# mem.net
KiCad netlist of a schematic drawn in EAGLE
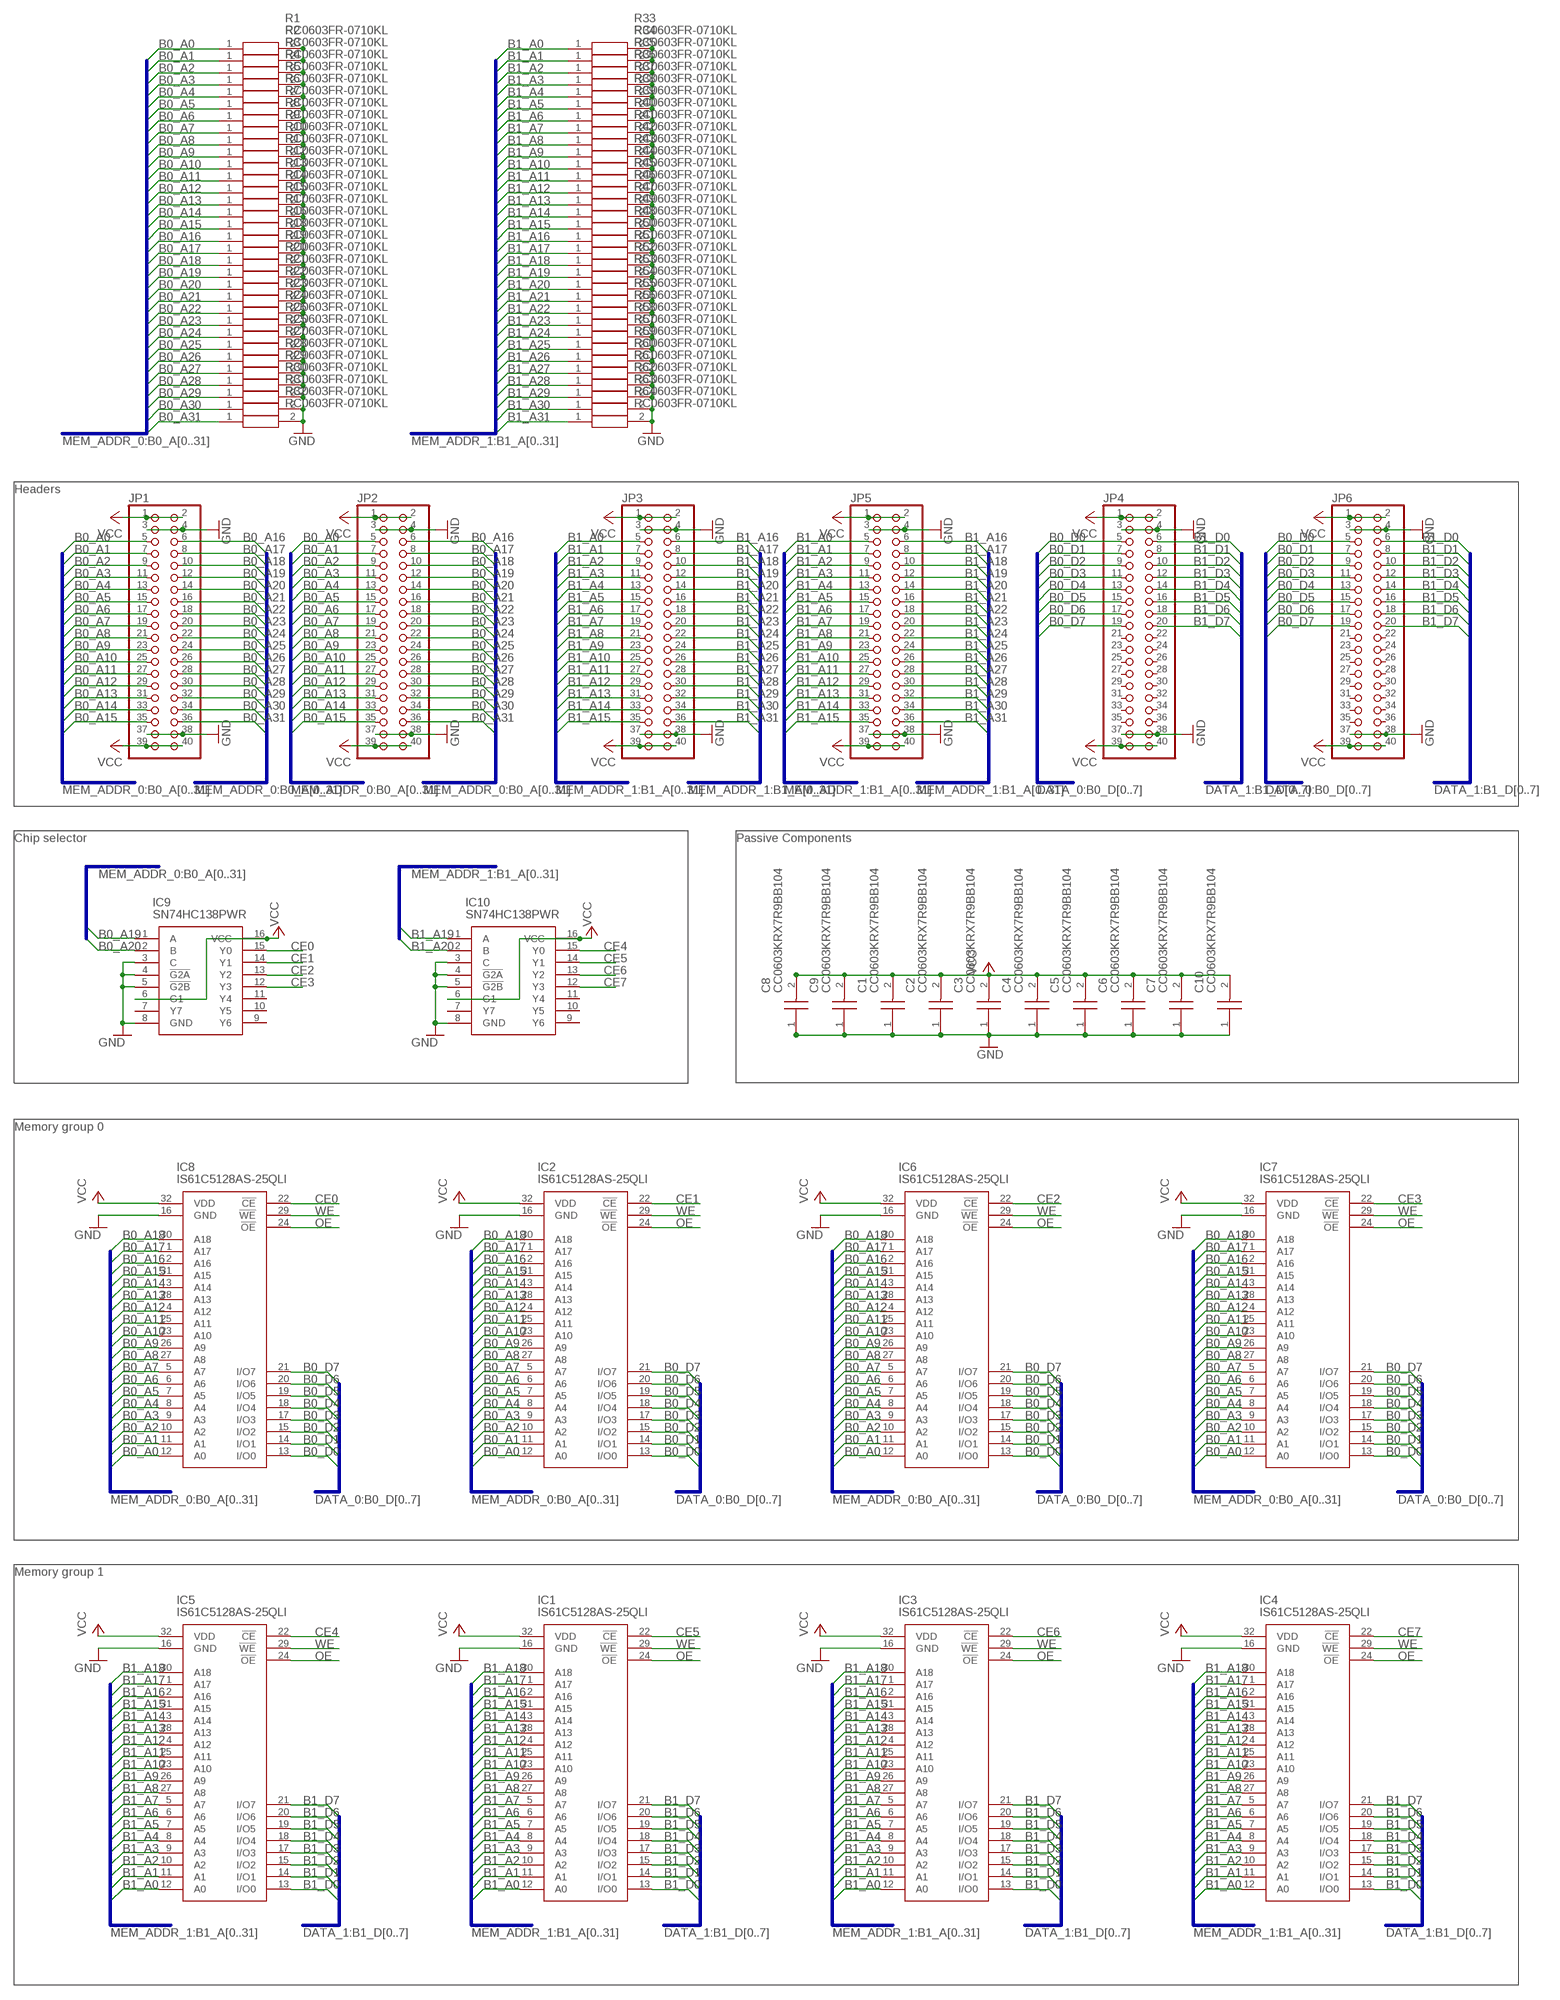
[diagram p0: schematic, sheet 1]

(export (version "E")
  (design (tool "Eeschema 10.0.6"))
  (components
    (comp (ref "C1")
      (value "CC0603KRX7R9BB104")
      (footprint "eagle-import:CAPC1608X90N")
      (fields (field (name "MOUSER_PART_NUMBER") "603-CC603KRX7R9BB104"))
      (libsource (lib "eagle-import") (part "CC0603KRX7R9BB104"))
    )
    (comp (ref "C2")
      (value "CC0603KRX7R9BB104")
      (footprint "eagle-import:CAPC1608X90N")
      (fields (field (name "MOUSER_PART_NUMBER") "603-CC603KRX7R9BB104"))
      (libsource (lib "eagle-import") (part "CC0603KRX7R9BB104"))
    )
    (comp (ref "C3")
      (value "CC0603KRX7R9BB104")
      (footprint "eagle-import:CAPC1608X90N")
      (fields (field (name "MOUSER_PART_NUMBER") "603-CC603KRX7R9BB104"))
      (libsource (lib "eagle-import") (part "CC0603KRX7R9BB104"))
    )
    (comp (ref "C4")
      (value "CC0603KRX7R9BB104")
      (footprint "eagle-import:CAPC1608X90N")
      (fields (field (name "MOUSER_PART_NUMBER") "603-CC603KRX7R9BB104"))
      (libsource (lib "eagle-import") (part "CC0603KRX7R9BB104"))
    )
    (comp (ref "C5")
      (value "CC0603KRX7R9BB104")
      (footprint "eagle-import:CAPC1608X90N")
      (fields (field (name "MOUSER_PART_NUMBER") "603-CC603KRX7R9BB104"))
      (libsource (lib "eagle-import") (part "CC0603KRX7R9BB104"))
    )
    (comp (ref "C6")
      (value "CC0603KRX7R9BB104")
      (footprint "eagle-import:CAPC1608X90N")
      (fields (field (name "MOUSER_PART_NUMBER") "603-CC603KRX7R9BB104"))
      (libsource (lib "eagle-import") (part "CC0603KRX7R9BB104"))
    )
    (comp (ref "C7")
      (value "CC0603KRX7R9BB104")
      (footprint "eagle-import:CAPC1608X90N")
      (fields (field (name "MOUSER_PART_NUMBER") "603-CC603KRX7R9BB104"))
      (libsource (lib "eagle-import") (part "CC0603KRX7R9BB104"))
    )
    (comp (ref "C8")
      (value "CC0603KRX7R9BB104")
      (footprint "eagle-import:CAPC1608X90N")
      (fields (field (name "MOUSER_PART_NUMBER") "603-CC603KRX7R9BB104"))
      (libsource (lib "eagle-import") (part "CC0603KRX7R9BB104"))
    )
    (comp (ref "C9")
      (value "CC0603KRX7R9BB104")
      (footprint "eagle-import:CAPC1608X90N")
      (fields (field (name "MOUSER_PART_NUMBER") "603-CC603KRX7R9BB104"))
      (libsource (lib "eagle-import") (part "CC0603KRX7R9BB104"))
    )
    (comp (ref "C10")
      (value "CC0603KRX7R9BB104")
      (footprint "eagle-import:CAPC1608X90N")
      (fields (field (name "MOUSER_PART_NUMBER") "603-CC603KRX7R9BB104"))
      (libsource (lib "eagle-import") (part "CC0603KRX7R9BB104"))
    )
    (comp (ref "IC1")
      (value "IS61C5128AS-25QLI")
      (footprint "eagle-import:SOIC127P1412X305-32N")
      (fields (field (name "MOUSER_PART_NUMBER") "870-61C5128AS-25QLI"))
      (libsource (lib "eagle-import") (part "IS61C5128AS-25QLI"))
    )
    (comp (ref "IC2")
      (value "IS61C5128AS-25QLI")
      (footprint "eagle-import:SOIC127P1412X305-32N")
      (fields (field (name "MOUSER_PART_NUMBER") "870-61C5128AS-25QLI"))
      (libsource (lib "eagle-import") (part "IS61C5128AS-25QLI"))
    )
    (comp (ref "IC3")
      (value "IS61C5128AS-25QLI")
      (footprint "eagle-import:SOIC127P1412X305-32N")
      (fields (field (name "MOUSER_PART_NUMBER") "870-61C5128AS-25QLI"))
      (libsource (lib "eagle-import") (part "IS61C5128AS-25QLI"))
    )
    (comp (ref "IC4")
      (value "IS61C5128AS-25QLI")
      (footprint "eagle-import:SOIC127P1412X305-32N")
      (fields (field (name "MOUSER_PART_NUMBER") "870-61C5128AS-25QLI"))
      (libsource (lib "eagle-import") (part "IS61C5128AS-25QLI"))
    )
    (comp (ref "IC5")
      (value "IS61C5128AS-25QLI")
      (footprint "eagle-import:SOIC127P1412X305-32N")
      (fields (field (name "MOUSER_PART_NUMBER") "870-61C5128AS-25QLI"))
      (libsource (lib "eagle-import") (part "IS61C5128AS-25QLI"))
    )
    (comp (ref "IC6")
      (value "IS61C5128AS-25QLI")
      (footprint "eagle-import:SOIC127P1412X305-32N")
      (fields (field (name "MOUSER_PART_NUMBER") "870-61C5128AS-25QLI"))
      (libsource (lib "eagle-import") (part "IS61C5128AS-25QLI"))
    )
    (comp (ref "IC7")
      (value "IS61C5128AS-25QLI")
      (footprint "eagle-import:SOIC127P1412X305-32N")
      (fields (field (name "MOUSER_PART_NUMBER") "870-61C5128AS-25QLI"))
      (libsource (lib "eagle-import") (part "IS61C5128AS-25QLI"))
    )
    (comp (ref "IC8")
      (value "IS61C5128AS-25QLI")
      (footprint "eagle-import:SOIC127P1412X305-32N")
      (fields (field (name "MOUSER_PART_NUMBER") "870-61C5128AS-25QLI"))
      (libsource (lib "eagle-import") (part "IS61C5128AS-25QLI"))
    )
    (comp (ref "IC9")
      (value "SN74HC138PWR")
      (footprint "eagle-import:SOP65P640X120-16N")
      (fields (field (name "MOUSER_PART_NUMBER") "595-SN74HC138PWR"))
      (libsource (lib "eagle-import") (part "SN74HC138PWR"))
    )
    (comp (ref "IC10")
      (value "SN74HC138PWR")
      (footprint "eagle-import:SOP65P640X120-16N")
      (fields (field (name "MOUSER_PART_NUMBER") "595-SN74HC138PWR"))
      (libsource (lib "eagle-import") (part "SN74HC138PWR"))
    )
    (comp (ref "JP1")
      (value "PINHD-2X20")
      (footprint "eagle-import:2X20")
      (libsource (lib "eagle-import") (part "PINHD-2X20"))
    )
    (comp (ref "JP2")
      (value "PINHD-2X20")
      (footprint "eagle-import:2X20")
      (libsource (lib "eagle-import") (part "PINHD-2X20"))
    )
    (comp (ref "JP3")
      (value "PINHD-2X20")
      (footprint "eagle-import:2X20")
      (libsource (lib "eagle-import") (part "PINHD-2X20"))
    )
    (comp (ref "JP4")
      (value "PINHD-2X20")
      (footprint "eagle-import:2X20")
      (libsource (lib "eagle-import") (part "PINHD-2X20"))
    )
    (comp (ref "JP5")
      (value "PINHD-2X20")
      (footprint "eagle-import:2X20")
      (libsource (lib "eagle-import") (part "PINHD-2X20"))
    )
    (comp (ref "JP6")
      (value "PINHD-2X20")
      (footprint "eagle-import:2X20")
      (libsource (lib "eagle-import") (part "PINHD-2X20"))
    )
    (comp (ref "R1")
      (value "RC0603FR-0710KL")
      (footprint "eagle-import:RESC1608X55N")
      (fields (field (name "MOUSER_PART_NUMBER") "603-RC0603FR-0710KL"))
      (libsource (lib "eagle-import") (part "RC0603FR-0710KL"))
    )
    (comp (ref "R2")
      (value "RC0603FR-0710KL")
      (footprint "eagle-import:RESC1608X55N")
      (fields (field (name "MOUSER_PART_NUMBER") "603-RC0603FR-0710KL"))
      (libsource (lib "eagle-import") (part "RC0603FR-0710KL"))
    )
    (comp (ref "R3")
      (value "RC0603FR-0710KL")
      (footprint "eagle-import:RESC1608X55N")
      (fields (field (name "MOUSER_PART_NUMBER") "603-RC0603FR-0710KL"))
      (libsource (lib "eagle-import") (part "RC0603FR-0710KL"))
    )
    (comp (ref "R4")
      (value "RC0603FR-0710KL")
      (footprint "eagle-import:RESC1608X55N")
      (fields (field (name "MOUSER_PART_NUMBER") "603-RC0603FR-0710KL"))
      (libsource (lib "eagle-import") (part "RC0603FR-0710KL"))
    )
    (comp (ref "R5")
      (value "RC0603FR-0710KL")
      (footprint "eagle-import:RESC1608X55N")
      (fields (field (name "MOUSER_PART_NUMBER") "603-RC0603FR-0710KL"))
      (libsource (lib "eagle-import") (part "RC0603FR-0710KL"))
    )
    (comp (ref "R6")
      (value "RC0603FR-0710KL")
      (footprint "eagle-import:RESC1608X55N")
      (fields (field (name "MOUSER_PART_NUMBER") "603-RC0603FR-0710KL"))
      (libsource (lib "eagle-import") (part "RC0603FR-0710KL"))
    )
    (comp (ref "R7")
      (value "RC0603FR-0710KL")
      (footprint "eagle-import:RESC1608X55N")
      (fields (field (name "MOUSER_PART_NUMBER") "603-RC0603FR-0710KL"))
      (libsource (lib "eagle-import") (part "RC0603FR-0710KL"))
    )
    (comp (ref "R8")
      (value "RC0603FR-0710KL")
      (footprint "eagle-import:RESC1608X55N")
      (fields (field (name "MOUSER_PART_NUMBER") "603-RC0603FR-0710KL"))
      (libsource (lib "eagle-import") (part "RC0603FR-0710KL"))
    )
    (comp (ref "R9")
      (value "RC0603FR-0710KL")
      (footprint "eagle-import:RESC1608X55N")
      (fields (field (name "MOUSER_PART_NUMBER") "603-RC0603FR-0710KL"))
      (libsource (lib "eagle-import") (part "RC0603FR-0710KL"))
    )
    (comp (ref "R10")
      (value "RC0603FR-0710KL")
      (footprint "eagle-import:RESC1608X55N")
      (fields (field (name "MOUSER_PART_NUMBER") "603-RC0603FR-0710KL"))
      (libsource (lib "eagle-import") (part "RC0603FR-0710KL"))
    )
    (comp (ref "R11")
      (value "RC0603FR-0710KL")
      (footprint "eagle-import:RESC1608X55N")
      (fields (field (name "MOUSER_PART_NUMBER") "603-RC0603FR-0710KL"))
      (libsource (lib "eagle-import") (part "RC0603FR-0710KL"))
    )
    (comp (ref "R12")
      (value "RC0603FR-0710KL")
      (footprint "eagle-import:RESC1608X55N")
      (fields (field (name "MOUSER_PART_NUMBER") "603-RC0603FR-0710KL"))
      (libsource (lib "eagle-import") (part "RC0603FR-0710KL"))
    )
    (comp (ref "R13")
      (value "RC0603FR-0710KL")
      (footprint "eagle-import:RESC1608X55N")
      (fields (field (name "MOUSER_PART_NUMBER") "603-RC0603FR-0710KL"))
      (libsource (lib "eagle-import") (part "RC0603FR-0710KL"))
    )
    (comp (ref "R14")
      (value "RC0603FR-0710KL")
      (footprint "eagle-import:RESC1608X55N")
      (fields (field (name "MOUSER_PART_NUMBER") "603-RC0603FR-0710KL"))
      (libsource (lib "eagle-import") (part "RC0603FR-0710KL"))
    )
    (comp (ref "R15")
      (value "RC0603FR-0710KL")
      (footprint "eagle-import:RESC1608X55N")
      (fields (field (name "MOUSER_PART_NUMBER") "603-RC0603FR-0710KL"))
      (libsource (lib "eagle-import") (part "RC0603FR-0710KL"))
    )
    (comp (ref "R16")
      (value "RC0603FR-0710KL")
      (footprint "eagle-import:RESC1608X55N")
      (fields (field (name "MOUSER_PART_NUMBER") "603-RC0603FR-0710KL"))
      (libsource (lib "eagle-import") (part "RC0603FR-0710KL"))
    )
    (comp (ref "R17")
      (value "RC0603FR-0710KL")
      (footprint "eagle-import:RESC1608X55N")
      (fields (field (name "MOUSER_PART_NUMBER") "603-RC0603FR-0710KL"))
      (libsource (lib "eagle-import") (part "RC0603FR-0710KL"))
    )
    (comp (ref "R18")
      (value "RC0603FR-0710KL")
      (footprint "eagle-import:RESC1608X55N")
      (fields (field (name "MOUSER_PART_NUMBER") "603-RC0603FR-0710KL"))
      (libsource (lib "eagle-import") (part "RC0603FR-0710KL"))
    )
    (comp (ref "R19")
      (value "RC0603FR-0710KL")
      (footprint "eagle-import:RESC1608X55N")
      (fields (field (name "MOUSER_PART_NUMBER") "603-RC0603FR-0710KL"))
      (libsource (lib "eagle-import") (part "RC0603FR-0710KL"))
    )
    (comp (ref "R20")
      (value "RC0603FR-0710KL")
      (footprint "eagle-import:RESC1608X55N")
      (fields (field (name "MOUSER_PART_NUMBER") "603-RC0603FR-0710KL"))
      (libsource (lib "eagle-import") (part "RC0603FR-0710KL"))
    )
    (comp (ref "R21")
      (value "RC0603FR-0710KL")
      (footprint "eagle-import:RESC1608X55N")
      (fields (field (name "MOUSER_PART_NUMBER") "603-RC0603FR-0710KL"))
      (libsource (lib "eagle-import") (part "RC0603FR-0710KL"))
    )
    (comp (ref "R22")
      (value "RC0603FR-0710KL")
      (footprint "eagle-import:RESC1608X55N")
      (fields (field (name "MOUSER_PART_NUMBER") "603-RC0603FR-0710KL"))
      (libsource (lib "eagle-import") (part "RC0603FR-0710KL"))
    )
    (comp (ref "R23")
      (value "RC0603FR-0710KL")
      (footprint "eagle-import:RESC1608X55N")
      (fields (field (name "MOUSER_PART_NUMBER") "603-RC0603FR-0710KL"))
      (libsource (lib "eagle-import") (part "RC0603FR-0710KL"))
    )
    (comp (ref "R24")
      (value "RC0603FR-0710KL")
      (footprint "eagle-import:RESC1608X55N")
      (fields (field (name "MOUSER_PART_NUMBER") "603-RC0603FR-0710KL"))
      (libsource (lib "eagle-import") (part "RC0603FR-0710KL"))
    )
    (comp (ref "R25")
      (value "RC0603FR-0710KL")
      (footprint "eagle-import:RESC1608X55N")
      (fields (field (name "MOUSER_PART_NUMBER") "603-RC0603FR-0710KL"))
      (libsource (lib "eagle-import") (part "RC0603FR-0710KL"))
    )
    (comp (ref "R26")
      (value "RC0603FR-0710KL")
      (footprint "eagle-import:RESC1608X55N")
      (fields (field (name "MOUSER_PART_NUMBER") "603-RC0603FR-0710KL"))
      (libsource (lib "eagle-import") (part "RC0603FR-0710KL"))
    )
    (comp (ref "R27")
      (value "RC0603FR-0710KL")
      (footprint "eagle-import:RESC1608X55N")
      (fields (field (name "MOUSER_PART_NUMBER") "603-RC0603FR-0710KL"))
      (libsource (lib "eagle-import") (part "RC0603FR-0710KL"))
    )
    (comp (ref "R28")
      (value "RC0603FR-0710KL")
      (footprint "eagle-import:RESC1608X55N")
      (fields (field (name "MOUSER_PART_NUMBER") "603-RC0603FR-0710KL"))
      (libsource (lib "eagle-import") (part "RC0603FR-0710KL"))
    )
    (comp (ref "R29")
      (value "RC0603FR-0710KL")
      (footprint "eagle-import:RESC1608X55N")
      (fields (field (name "MOUSER_PART_NUMBER") "603-RC0603FR-0710KL"))
      (libsource (lib "eagle-import") (part "RC0603FR-0710KL"))
    )
    (comp (ref "R30")
      (value "RC0603FR-0710KL")
      (footprint "eagle-import:RESC1608X55N")
      (fields (field (name "MOUSER_PART_NUMBER") "603-RC0603FR-0710KL"))
      (libsource (lib "eagle-import") (part "RC0603FR-0710KL"))
    )
    (comp (ref "R31")
      (value "RC0603FR-0710KL")
      (footprint "eagle-import:RESC1608X55N")
      (fields (field (name "MOUSER_PART_NUMBER") "603-RC0603FR-0710KL"))
      (libsource (lib "eagle-import") (part "RC0603FR-0710KL"))
    )
    (comp (ref "R32")
      (value "RC0603FR-0710KL")
      (footprint "eagle-import:RESC1608X55N")
      (fields (field (name "MOUSER_PART_NUMBER") "603-RC0603FR-0710KL"))
      (libsource (lib "eagle-import") (part "RC0603FR-0710KL"))
    )
    (comp (ref "R33")
      (value "RC0603FR-0710KL")
      (footprint "eagle-import:RESC1608X55N")
      (fields (field (name "MOUSER_PART_NUMBER") "603-RC0603FR-0710KL"))
      (libsource (lib "eagle-import") (part "RC0603FR-0710KL"))
    )
    (comp (ref "R34")
      (value "RC0603FR-0710KL")
      (footprint "eagle-import:RESC1608X55N")
      (fields (field (name "MOUSER_PART_NUMBER") "603-RC0603FR-0710KL"))
      (libsource (lib "eagle-import") (part "RC0603FR-0710KL"))
    )
    (comp (ref "R35")
      (value "RC0603FR-0710KL")
      (footprint "eagle-import:RESC1608X55N")
      (fields (field (name "MOUSER_PART_NUMBER") "603-RC0603FR-0710KL"))
      (libsource (lib "eagle-import") (part "RC0603FR-0710KL"))
    )
    (comp (ref "R36")
      (value "RC0603FR-0710KL")
      (footprint "eagle-import:RESC1608X55N")
      (fields (field (name "MOUSER_PART_NUMBER") "603-RC0603FR-0710KL"))
      (libsource (lib "eagle-import") (part "RC0603FR-0710KL"))
    )
    (comp (ref "R37")
      (value "RC0603FR-0710KL")
      (footprint "eagle-import:RESC1608X55N")
      (fields (field (name "MOUSER_PART_NUMBER") "603-RC0603FR-0710KL"))
      (libsource (lib "eagle-import") (part "RC0603FR-0710KL"))
    )
    (comp (ref "R38")
      (value "RC0603FR-0710KL")
      (footprint "eagle-import:RESC1608X55N")
      (fields (field (name "MOUSER_PART_NUMBER") "603-RC0603FR-0710KL"))
      (libsource (lib "eagle-import") (part "RC0603FR-0710KL"))
    )
    (comp (ref "R39")
      (value "RC0603FR-0710KL")
      (footprint "eagle-import:RESC1608X55N")
      (fields (field (name "MOUSER_PART_NUMBER") "603-RC0603FR-0710KL"))
      (libsource (lib "eagle-import") (part "RC0603FR-0710KL"))
    )
    (comp (ref "R40")
      (value "RC0603FR-0710KL")
      (footprint "eagle-import:RESC1608X55N")
      (fields (field (name "MOUSER_PART_NUMBER") "603-RC0603FR-0710KL"))
      (libsource (lib "eagle-import") (part "RC0603FR-0710KL"))
    )
    (comp (ref "R41")
      (value "RC0603FR-0710KL")
      (footprint "eagle-import:RESC1608X55N")
      (fields (field (name "MOUSER_PART_NUMBER") "603-RC0603FR-0710KL"))
      (libsource (lib "eagle-import") (part "RC0603FR-0710KL"))
    )
    (comp (ref "R42")
      (value "RC0603FR-0710KL")
      (footprint "eagle-import:RESC1608X55N")
      (fields (field (name "MOUSER_PART_NUMBER") "603-RC0603FR-0710KL"))
      (libsource (lib "eagle-import") (part "RC0603FR-0710KL"))
    )
    (comp (ref "R43")
      (value "RC0603FR-0710KL")
      (footprint "eagle-import:RESC1608X55N")
      (fields (field (name "MOUSER_PART_NUMBER") "603-RC0603FR-0710KL"))
      (libsource (lib "eagle-import") (part "RC0603FR-0710KL"))
    )
    (comp (ref "R44")
      (value "RC0603FR-0710KL")
      (footprint "eagle-import:RESC1608X55N")
      (fields (field (name "MOUSER_PART_NUMBER") "603-RC0603FR-0710KL"))
      (libsource (lib "eagle-import") (part "RC0603FR-0710KL"))
    )
    (comp (ref "R45")
      (value "RC0603FR-0710KL")
      (footprint "eagle-import:RESC1608X55N")
      (fields (field (name "MOUSER_PART_NUMBER") "603-RC0603FR-0710KL"))
      (libsource (lib "eagle-import") (part "RC0603FR-0710KL"))
    )
    (comp (ref "R46")
      (value "RC0603FR-0710KL")
      (footprint "eagle-import:RESC1608X55N")
      (fields (field (name "MOUSER_PART_NUMBER") "603-RC0603FR-0710KL"))
      (libsource (lib "eagle-import") (part "RC0603FR-0710KL"))
    )
    (comp (ref "R47")
      (value "RC0603FR-0710KL")
      (footprint "eagle-import:RESC1608X55N")
      (fields (field (name "MOUSER_PART_NUMBER") "603-RC0603FR-0710KL"))
      (libsource (lib "eagle-import") (part "RC0603FR-0710KL"))
    )
    (comp (ref "R48")
      (value "RC0603FR-0710KL")
      (footprint "eagle-import:RESC1608X55N")
      (fields (field (name "MOUSER_PART_NUMBER") "603-RC0603FR-0710KL"))
      (libsource (lib "eagle-import") (part "RC0603FR-0710KL"))
    )
    (comp (ref "R49")
      (value "RC0603FR-0710KL")
      (footprint "eagle-import:RESC1608X55N")
      (fields (field (name "MOUSER_PART_NUMBER") "603-RC0603FR-0710KL"))
      (libsource (lib "eagle-import") (part "RC0603FR-0710KL"))
    )
    (comp (ref "R50")
      (value "RC0603FR-0710KL")
      (footprint "eagle-import:RESC1608X55N")
      (fields (field (name "MOUSER_PART_NUMBER") "603-RC0603FR-0710KL"))
      (libsource (lib "eagle-import") (part "RC0603FR-0710KL"))
    )
    (comp (ref "R51")
      (value "RC0603FR-0710KL")
      (footprint "eagle-import:RESC1608X55N")
      (fields (field (name "MOUSER_PART_NUMBER") "603-RC0603FR-0710KL"))
      (libsource (lib "eagle-import") (part "RC0603FR-0710KL"))
    )
    (comp (ref "R52")
      (value "RC0603FR-0710KL")
      (footprint "eagle-import:RESC1608X55N")
      (fields (field (name "MOUSER_PART_NUMBER") "603-RC0603FR-0710KL"))
      (libsource (lib "eagle-import") (part "RC0603FR-0710KL"))
    )
    (comp (ref "R53")
      (value "RC0603FR-0710KL")
      (footprint "eagle-import:RESC1608X55N")
      (fields (field (name "MOUSER_PART_NUMBER") "603-RC0603FR-0710KL"))
      (libsource (lib "eagle-import") (part "RC0603FR-0710KL"))
    )
    (comp (ref "R54")
      (value "RC0603FR-0710KL")
      (footprint "eagle-import:RESC1608X55N")
      (fields (field (name "MOUSER_PART_NUMBER") "603-RC0603FR-0710KL"))
      (libsource (lib "eagle-import") (part "RC0603FR-0710KL"))
    )
    (comp (ref "R55")
      (value "RC0603FR-0710KL")
      (footprint "eagle-import:RESC1608X55N")
      (fields (field (name "MOUSER_PART_NUMBER") "603-RC0603FR-0710KL"))
      (libsource (lib "eagle-import") (part "RC0603FR-0710KL"))
    )
    (comp (ref "R56")
      (value "RC0603FR-0710KL")
      (footprint "eagle-import:RESC1608X55N")
      (fields (field (name "MOUSER_PART_NUMBER") "603-RC0603FR-0710KL"))
      (libsource (lib "eagle-import") (part "RC0603FR-0710KL"))
    )
    (comp (ref "R57")
      (value "RC0603FR-0710KL")
      (footprint "eagle-import:RESC1608X55N")
      (fields (field (name "MOUSER_PART_NUMBER") "603-RC0603FR-0710KL"))
      (libsource (lib "eagle-import") (part "RC0603FR-0710KL"))
    )
    (comp (ref "R58")
      (value "RC0603FR-0710KL")
      (footprint "eagle-import:RESC1608X55N")
      (fields (field (name "MOUSER_PART_NUMBER") "603-RC0603FR-0710KL"))
      (libsource (lib "eagle-import") (part "RC0603FR-0710KL"))
    )
    (comp (ref "R59")
      (value "RC0603FR-0710KL")
      (footprint "eagle-import:RESC1608X55N")
      (fields (field (name "MOUSER_PART_NUMBER") "603-RC0603FR-0710KL"))
      (libsource (lib "eagle-import") (part "RC0603FR-0710KL"))
    )
    (comp (ref "R60")
      (value "RC0603FR-0710KL")
      (footprint "eagle-import:RESC1608X55N")
      (fields (field (name "MOUSER_PART_NUMBER") "603-RC0603FR-0710KL"))
      (libsource (lib "eagle-import") (part "RC0603FR-0710KL"))
    )
    (comp (ref "R61")
      (value "RC0603FR-0710KL")
      (footprint "eagle-import:RESC1608X55N")
      (fields (field (name "MOUSER_PART_NUMBER") "603-RC0603FR-0710KL"))
      (libsource (lib "eagle-import") (part "RC0603FR-0710KL"))
    )
    (comp (ref "R62")
      (value "RC0603FR-0710KL")
      (footprint "eagle-import:RESC1608X55N")
      (fields (field (name "MOUSER_PART_NUMBER") "603-RC0603FR-0710KL"))
      (libsource (lib "eagle-import") (part "RC0603FR-0710KL"))
    )
    (comp (ref "R63")
      (value "RC0603FR-0710KL")
      (footprint "eagle-import:RESC1608X55N")
      (fields (field (name "MOUSER_PART_NUMBER") "603-RC0603FR-0710KL"))
      (libsource (lib "eagle-import") (part "RC0603FR-0710KL"))
    )
    (comp (ref "R64")
      (value "RC0603FR-0710KL")
      (footprint "eagle-import:RESC1608X55N")
      (fields (field (name "MOUSER_PART_NUMBER") "603-RC0603FR-0710KL"))
      (libsource (lib "eagle-import") (part "RC0603FR-0710KL"))
    )
  )
  (nets
    (net (code "81") (name "/B0_A0") (class "Default")
      (node (ref "IC2") (pin "12") (pinfunction "A0_12") (pintype "bidirectional"))
      (node (ref "IC6") (pin "12") (pinfunction "A0_12") (pintype "bidirectional"))
      (node (ref "IC7") (pin "12") (pinfunction "A0_12") (pintype "bidirectional"))
      (node (ref "IC8") (pin "12") (pinfunction "A0_12") (pintype "bidirectional"))
      (node (ref "JP1") (pin "5") (pinfunction "5_5") (pintype "passive"))
      (node (ref "JP2") (pin "5") (pinfunction "5_5") (pintype "passive"))
      (node (ref "R1") (pin "1") (pinfunction "1_1") (pintype "bidirectional"))
    )
    (net (code "82") (name "/B0_A1") (class "Default")
      (node (ref "IC2") (pin "11") (pinfunction "A1_11") (pintype "bidirectional"))
      (node (ref "IC6") (pin "11") (pinfunction "A1_11") (pintype "bidirectional"))
      (node (ref "IC7") (pin "11") (pinfunction "A1_11") (pintype "bidirectional"))
      (node (ref "IC8") (pin "11") (pinfunction "A1_11") (pintype "bidirectional"))
      (node (ref "JP1") (pin "7") (pinfunction "7_7") (pintype "passive"))
      (node (ref "JP2") (pin "7") (pinfunction "7_7") (pintype "passive"))
      (node (ref "R2") (pin "1") (pinfunction "1_1") (pintype "bidirectional"))
    )
    (net (code "83") (name "/B0_A2") (class "Default")
      (node (ref "IC2") (pin "10") (pinfunction "A2_10") (pintype "bidirectional"))
      (node (ref "IC6") (pin "10") (pinfunction "A2_10") (pintype "bidirectional"))
      (node (ref "IC7") (pin "10") (pinfunction "A2_10") (pintype "bidirectional"))
      (node (ref "IC8") (pin "10") (pinfunction "A2_10") (pintype "bidirectional"))
      (node (ref "JP1") (pin "9") (pinfunction "9_9") (pintype "passive"))
      (node (ref "JP2") (pin "9") (pinfunction "9_9") (pintype "passive"))
      (node (ref "R3") (pin "1") (pinfunction "1_1") (pintype "bidirectional"))
    )
    (net (code "84") (name "/B0_A3") (class "Default")
      (node (ref "IC2") (pin "9") (pinfunction "A3_9") (pintype "bidirectional"))
      (node (ref "IC6") (pin "9") (pinfunction "A3_9") (pintype "bidirectional"))
      (node (ref "IC7") (pin "9") (pinfunction "A3_9") (pintype "bidirectional"))
      (node (ref "IC8") (pin "9") (pinfunction "A3_9") (pintype "bidirectional"))
      (node (ref "JP1") (pin "11") (pinfunction "11_11") (pintype "passive"))
      (node (ref "JP2") (pin "11") (pinfunction "11_11") (pintype "passive"))
      (node (ref "R4") (pin "1") (pinfunction "1_1") (pintype "bidirectional"))
    )
    (net (code "85") (name "/B0_A4") (class "Default")
      (node (ref "IC2") (pin "8") (pinfunction "A4_8") (pintype "bidirectional"))
      (node (ref "IC6") (pin "8") (pinfunction "A4_8") (pintype "bidirectional"))
      (node (ref "IC7") (pin "8") (pinfunction "A4_8") (pintype "bidirectional"))
      (node (ref "IC8") (pin "8") (pinfunction "A4_8") (pintype "bidirectional"))
      (node (ref "JP1") (pin "13") (pinfunction "13_13") (pintype "passive"))
      (node (ref "JP2") (pin "13") (pinfunction "13_13") (pintype "passive"))
      (node (ref "R5") (pin "1") (pinfunction "1_1") (pintype "bidirectional"))
    )
    (net (code "86") (name "/B0_A5") (class "Default")
      (node (ref "IC2") (pin "7") (pinfunction "A5_7") (pintype "bidirectional"))
      (node (ref "IC6") (pin "7") (pinfunction "A5_7") (pintype "bidirectional"))
      (node (ref "IC7") (pin "7") (pinfunction "A5_7") (pintype "bidirectional"))
      (node (ref "IC8") (pin "7") (pinfunction "A5_7") (pintype "bidirectional"))
      (node (ref "JP1") (pin "15") (pinfunction "15_15") (pintype "passive"))
      (node (ref "JP2") (pin "15") (pinfunction "15_15") (pintype "passive"))
      (node (ref "R6") (pin "1") (pinfunction "1_1") (pintype "bidirectional"))
    )
    (net (code "87") (name "/B0_A6") (class "Default")
      (node (ref "IC2") (pin "6") (pinfunction "A6_6") (pintype "bidirectional"))
      (node (ref "IC6") (pin "6") (pinfunction "A6_6") (pintype "bidirectional"))
      (node (ref "IC7") (pin "6") (pinfunction "A6_6") (pintype "bidirectional"))
      (node (ref "IC8") (pin "6") (pinfunction "A6_6") (pintype "bidirectional"))
      (node (ref "JP1") (pin "17") (pinfunction "17_17") (pintype "passive"))
      (node (ref "JP2") (pin "17") (pinfunction "17_17") (pintype "passive"))
      (node (ref "R7") (pin "1") (pinfunction "1_1") (pintype "bidirectional"))
    )
    (net (code "88") (name "/B0_A7") (class "Default")
      (node (ref "IC2") (pin "5") (pinfunction "A7_5") (pintype "bidirectional"))
      (node (ref "IC6") (pin "5") (pinfunction "A7_5") (pintype "bidirectional"))
      (node (ref "IC7") (pin "5") (pinfunction "A7_5") (pintype "bidirectional"))
      (node (ref "IC8") (pin "5") (pinfunction "A7_5") (pintype "bidirectional"))
      (node (ref "JP1") (pin "19") (pinfunction "19_19") (pintype "passive"))
      (node (ref "JP2") (pin "19") (pinfunction "19_19") (pintype "passive"))
      (node (ref "R8") (pin "1") (pinfunction "1_1") (pintype "bidirectional"))
    )
    (net (code "89") (name "/B0_A8") (class "Default")
      (node (ref "IC2") (pin "27") (pinfunction "A8_27") (pintype "bidirectional"))
      (node (ref "IC6") (pin "27") (pinfunction "A8_27") (pintype "bidirectional"))
      (node (ref "IC7") (pin "27") (pinfunction "A8_27") (pintype "bidirectional"))
      (node (ref "IC8") (pin "27") (pinfunction "A8_27") (pintype "bidirectional"))
      (node (ref "JP1") (pin "21") (pinfunction "21_21") (pintype "passive"))
      (node (ref "JP2") (pin "21") (pinfunction "21_21") (pintype "passive"))
      (node (ref "R9") (pin "1") (pinfunction "1_1") (pintype "bidirectional"))
    )
    (net (code "90") (name "/B0_A9") (class "Default")
      (node (ref "IC2") (pin "26") (pinfunction "A9_26") (pintype "bidirectional"))
      (node (ref "IC6") (pin "26") (pinfunction "A9_26") (pintype "bidirectional"))
      (node (ref "IC7") (pin "26") (pinfunction "A9_26") (pintype "bidirectional"))
      (node (ref "IC8") (pin "26") (pinfunction "A9_26") (pintype "bidirectional"))
      (node (ref "JP1") (pin "23") (pinfunction "23_23") (pintype "passive"))
      (node (ref "JP2") (pin "23") (pinfunction "23_23") (pintype "passive"))
      (node (ref "R10") (pin "1") (pinfunction "1_1") (pintype "bidirectional"))
    )
    (net (code "91") (name "/B0_A10") (class "Default")
      (node (ref "IC2") (pin "23") (pinfunction "A10_23") (pintype "bidirectional"))
      (node (ref "IC6") (pin "23") (pinfunction "A10_23") (pintype "bidirectional"))
      (node (ref "IC7") (pin "23") (pinfunction "A10_23") (pintype "bidirectional"))
      (node (ref "IC8") (pin "23") (pinfunction "A10_23") (pintype "bidirectional"))
      (node (ref "JP1") (pin "25") (pinfunction "25_25") (pintype "passive"))
      (node (ref "JP2") (pin "25") (pinfunction "25_25") (pintype "passive"))
      (node (ref "R11") (pin "1") (pinfunction "1_1") (pintype "bidirectional"))
    )
    (net (code "92") (name "/B0_A11") (class "Default")
      (node (ref "IC2") (pin "25") (pinfunction "A11_25") (pintype "bidirectional"))
      (node (ref "IC6") (pin "25") (pinfunction "A11_25") (pintype "bidirectional"))
      (node (ref "IC7") (pin "25") (pinfunction "A11_25") (pintype "bidirectional"))
      (node (ref "IC8") (pin "25") (pinfunction "A11_25") (pintype "bidirectional"))
      (node (ref "JP1") (pin "27") (pinfunction "27_27") (pintype "passive"))
      (node (ref "JP2") (pin "27") (pinfunction "27_27") (pintype "passive"))
      (node (ref "R12") (pin "1") (pinfunction "1_1") (pintype "bidirectional"))
    )
    (net (code "93") (name "/B0_A12") (class "Default")
      (node (ref "IC2") (pin "4") (pinfunction "A12_4") (pintype "bidirectional"))
      (node (ref "IC6") (pin "4") (pinfunction "A12_4") (pintype "bidirectional"))
      (node (ref "IC7") (pin "4") (pinfunction "A12_4") (pintype "bidirectional"))
      (node (ref "IC8") (pin "4") (pinfunction "A12_4") (pintype "bidirectional"))
      (node (ref "JP1") (pin "29") (pinfunction "29_29") (pintype "passive"))
      (node (ref "JP2") (pin "29") (pinfunction "29_29") (pintype "passive"))
      (node (ref "R13") (pin "1") (pinfunction "1_1") (pintype "bidirectional"))
    )
    (net (code "94") (name "/B0_A13") (class "Default")
      (node (ref "IC2") (pin "28") (pinfunction "A13_28") (pintype "bidirectional"))
      (node (ref "IC6") (pin "28") (pinfunction "A13_28") (pintype "bidirectional"))
      (node (ref "IC7") (pin "28") (pinfunction "A13_28") (pintype "bidirectional"))
      (node (ref "IC8") (pin "28") (pinfunction "A13_28") (pintype "bidirectional"))
      (node (ref "JP1") (pin "31") (pinfunction "31_31") (pintype "passive"))
      (node (ref "JP2") (pin "31") (pinfunction "31_31") (pintype "passive"))
      (node (ref "R14") (pin "1") (pinfunction "1_1") (pintype "bidirectional"))
    )
    (net (code "95") (name "/B0_A14") (class "Default")
      (node (ref "IC2") (pin "3") (pinfunction "A14_3") (pintype "bidirectional"))
      (node (ref "IC6") (pin "3") (pinfunction "A14_3") (pintype "bidirectional"))
      (node (ref "IC7") (pin "3") (pinfunction "A14_3") (pintype "bidirectional"))
      (node (ref "IC8") (pin "3") (pinfunction "A14_3") (pintype "bidirectional"))
      (node (ref "JP1") (pin "33") (pinfunction "33_33") (pintype "passive"))
      (node (ref "JP2") (pin "33") (pinfunction "33_33") (pintype "passive"))
      (node (ref "R15") (pin "1") (pinfunction "1_1") (pintype "bidirectional"))
    )
    (net (code "96") (name "/B0_A15") (class "Default")
      (node (ref "IC2") (pin "31") (pinfunction "A15_31") (pintype "bidirectional"))
      (node (ref "IC6") (pin "31") (pinfunction "A15_31") (pintype "bidirectional"))
      (node (ref "IC7") (pin "31") (pinfunction "A15_31") (pintype "bidirectional"))
      (node (ref "IC8") (pin "31") (pinfunction "A15_31") (pintype "bidirectional"))
      (node (ref "JP1") (pin "35") (pinfunction "35_35") (pintype "passive"))
      (node (ref "JP2") (pin "35") (pinfunction "35_35") (pintype "passive"))
      (node (ref "R17") (pin "1") (pinfunction "1_1") (pintype "bidirectional"))
    )
    (net (code "97") (name "/B0_A16") (class "Default")
      (node (ref "IC2") (pin "2") (pinfunction "A16_2") (pintype "bidirectional"))
      (node (ref "IC6") (pin "2") (pinfunction "A16_2") (pintype "bidirectional"))
      (node (ref "IC7") (pin "2") (pinfunction "A16_2") (pintype "bidirectional"))
      (node (ref "IC8") (pin "2") (pinfunction "A16_2") (pintype "bidirectional"))
      (node (ref "JP1") (pin "6") (pinfunction "6_6") (pintype "passive"))
      (node (ref "JP2") (pin "6") (pinfunction "6_6") (pintype "passive"))
      (node (ref "R16") (pin "1") (pinfunction "1_1") (pintype "bidirectional"))
    )
    (net (code "98") (name "/B0_A17") (class "Default")
      (node (ref "IC2") (pin "1") (pinfunction "A17_1") (pintype "bidirectional"))
      (node (ref "IC6") (pin "1") (pinfunction "A17_1") (pintype "bidirectional"))
      (node (ref "IC7") (pin "1") (pinfunction "A17_1") (pintype "bidirectional"))
      (node (ref "IC8") (pin "1") (pinfunction "A17_1") (pintype "bidirectional"))
      (node (ref "JP1") (pin "8") (pinfunction "8_8") (pintype "passive"))
      (node (ref "JP2") (pin "8") (pinfunction "8_8") (pintype "passive"))
      (node (ref "R18") (pin "1") (pinfunction "1_1") (pintype "bidirectional"))
    )
    (net (code "99") (name "/B0_A18") (class "Default")
      (node (ref "IC2") (pin "30") (pinfunction "A18_30") (pintype "bidirectional"))
      (node (ref "IC6") (pin "30") (pinfunction "A18_30") (pintype "bidirectional"))
      (node (ref "IC7") (pin "30") (pinfunction "A18_30") (pintype "bidirectional"))
      (node (ref "IC8") (pin "30") (pinfunction "A18_30") (pintype "bidirectional"))
      (node (ref "JP1") (pin "10") (pinfunction "10_10") (pintype "passive"))
      (node (ref "JP2") (pin "10") (pinfunction "10_10") (pintype "passive"))
      (node (ref "R19") (pin "1") (pinfunction "1_1") (pintype "bidirectional"))
    )
    (net (code "100") (name "/B0_A19") (class "Default")
      (node (ref "IC9") (pin "1") (pinfunction "A_1") (pintype "bidirectional"))
      (node (ref "JP1") (pin "12") (pinfunction "12_12") (pintype "passive"))
      (node (ref "JP2") (pin "12") (pinfunction "12_12") (pintype "passive"))
      (node (ref "R20") (pin "1") (pinfunction "1_1") (pintype "bidirectional"))
    )
    (net (code "101") (name "/B0_A20") (class "Default")
      (node (ref "IC9") (pin "2") (pinfunction "B_2") (pintype "bidirectional"))
      (node (ref "JP1") (pin "14") (pinfunction "14_14") (pintype "passive"))
      (node (ref "JP2") (pin "14") (pinfunction "14_14") (pintype "passive"))
      (node (ref "R21") (pin "1") (pinfunction "1_1") (pintype "bidirectional"))
    )
    (net (code "102") (name "/B0_A21") (class "Default")
      (node (ref "JP1") (pin "16") (pinfunction "16_16") (pintype "passive"))
      (node (ref "JP2") (pin "16") (pinfunction "16_16") (pintype "passive"))
      (node (ref "R22") (pin "1") (pinfunction "1_1") (pintype "bidirectional"))
    )
    (net (code "103") (name "/B0_A22") (class "Default")
      (node (ref "JP1") (pin "18") (pinfunction "18_18") (pintype "passive"))
      (node (ref "JP2") (pin "18") (pinfunction "18_18") (pintype "passive"))
      (node (ref "R23") (pin "1") (pinfunction "1_1") (pintype "bidirectional"))
    )
    (net (code "104") (name "/B0_A23") (class "Default")
      (node (ref "JP1") (pin "20") (pinfunction "20_20") (pintype "passive"))
      (node (ref "JP2") (pin "20") (pinfunction "20_20") (pintype "passive"))
      (node (ref "R24") (pin "1") (pinfunction "1_1") (pintype "bidirectional"))
    )
    (net (code "105") (name "/B0_A24") (class "Default")
      (node (ref "JP1") (pin "22") (pinfunction "22_22") (pintype "passive"))
      (node (ref "JP2") (pin "22") (pinfunction "22_22") (pintype "passive"))
      (node (ref "R26") (pin "1") (pinfunction "1_1") (pintype "bidirectional"))
    )
    (net (code "106") (name "/B0_A25") (class "Default")
      (node (ref "JP1") (pin "24") (pinfunction "24_24") (pintype "passive"))
      (node (ref "JP2") (pin "24") (pinfunction "24_24") (pintype "passive"))
      (node (ref "R25") (pin "1") (pinfunction "1_1") (pintype "bidirectional"))
    )
    (net (code "107") (name "/B0_A26") (class "Default")
      (node (ref "JP1") (pin "26") (pinfunction "26_26") (pintype "passive"))
      (node (ref "JP2") (pin "26") (pinfunction "26_26") (pintype "passive"))
      (node (ref "R27") (pin "1") (pinfunction "1_1") (pintype "bidirectional"))
    )
    (net (code "108") (name "/B0_A27") (class "Default")
      (node (ref "JP1") (pin "28") (pinfunction "28_28") (pintype "passive"))
      (node (ref "JP2") (pin "28") (pinfunction "28_28") (pintype "passive"))
      (node (ref "R28") (pin "1") (pinfunction "1_1") (pintype "bidirectional"))
    )
    (net (code "109") (name "/B0_A28") (class "Default")
      (node (ref "JP1") (pin "30") (pinfunction "30_30") (pintype "passive"))
      (node (ref "JP2") (pin "30") (pinfunction "30_30") (pintype "passive"))
      (node (ref "R29") (pin "1") (pinfunction "1_1") (pintype "bidirectional"))
    )
    (net (code "110") (name "/B0_A29") (class "Default")
      (node (ref "JP1") (pin "32") (pinfunction "32_32") (pintype "passive"))
      (node (ref "JP2") (pin "32") (pinfunction "32_32") (pintype "passive"))
      (node (ref "R30") (pin "1") (pinfunction "1_1") (pintype "bidirectional"))
    )
    (net (code "111") (name "/B0_A30") (class "Default")
      (node (ref "JP1") (pin "34") (pinfunction "34_34") (pintype "passive"))
      (node (ref "JP2") (pin "34") (pinfunction "34_34") (pintype "passive"))
      (node (ref "R31") (pin "1") (pinfunction "1_1") (pintype "bidirectional"))
    )
    (net (code "112") (name "/B0_A31") (class "Default")
      (node (ref "JP1") (pin "36") (pinfunction "36_36") (pintype "passive"))
      (node (ref "JP2") (pin "36") (pinfunction "36_36") (pintype "passive"))
      (node (ref "R32") (pin "1") (pinfunction "1_1") (pintype "bidirectional"))
    )
    (net (code "113") (name "/B0_D0") (class "Default")
      (node (ref "IC2") (pin "13") (pinfunction "I/O0_13") (pintype "bidirectional"))
      (node (ref "IC6") (pin "13") (pinfunction "I/O0_13") (pintype "bidirectional"))
      (node (ref "IC7") (pin "13") (pinfunction "I/O0_13") (pintype "bidirectional"))
      (node (ref "IC8") (pin "13") (pinfunction "I/O0_13") (pintype "bidirectional"))
      (node (ref "JP4") (pin "5") (pinfunction "5_5") (pintype "passive"))
      (node (ref "JP6") (pin "5") (pinfunction "5_5") (pintype "passive"))
    )
    (net (code "114") (name "/B0_D1") (class "Default")
      (node (ref "IC2") (pin "14") (pinfunction "I/O1_14") (pintype "bidirectional"))
      (node (ref "IC6") (pin "14") (pinfunction "I/O1_14") (pintype "bidirectional"))
      (node (ref "IC7") (pin "14") (pinfunction "I/O1_14") (pintype "bidirectional"))
      (node (ref "IC8") (pin "14") (pinfunction "I/O1_14") (pintype "bidirectional"))
      (node (ref "JP4") (pin "7") (pinfunction "7_7") (pintype "passive"))
      (node (ref "JP6") (pin "7") (pinfunction "7_7") (pintype "passive"))
    )
    (net (code "115") (name "/B0_D2") (class "Default")
      (node (ref "IC2") (pin "15") (pinfunction "I/O2_15") (pintype "bidirectional"))
      (node (ref "IC6") (pin "15") (pinfunction "I/O2_15") (pintype "bidirectional"))
      (node (ref "IC7") (pin "15") (pinfunction "I/O2_15") (pintype "bidirectional"))
      (node (ref "IC8") (pin "15") (pinfunction "I/O2_15") (pintype "bidirectional"))
      (node (ref "JP4") (pin "9") (pinfunction "9_9") (pintype "passive"))
      (node (ref "JP6") (pin "9") (pinfunction "9_9") (pintype "passive"))
    )
    (net (code "116") (name "/B0_D3") (class "Default")
      (node (ref "IC2") (pin "17") (pinfunction "I/O3_17") (pintype "bidirectional"))
      (node (ref "IC6") (pin "17") (pinfunction "I/O3_17") (pintype "bidirectional"))
      (node (ref "IC7") (pin "17") (pinfunction "I/O3_17") (pintype "bidirectional"))
      (node (ref "IC8") (pin "17") (pinfunction "I/O3_17") (pintype "bidirectional"))
      (node (ref "JP4") (pin "11") (pinfunction "11_11") (pintype "passive"))
      (node (ref "JP6") (pin "11") (pinfunction "11_11") (pintype "passive"))
    )
    (net (code "117") (name "/B0_D4") (class "Default")
      (node (ref "IC2") (pin "18") (pinfunction "I/O4_18") (pintype "bidirectional"))
      (node (ref "IC6") (pin "18") (pinfunction "I/O4_18") (pintype "bidirectional"))
      (node (ref "IC7") (pin "18") (pinfunction "I/O4_18") (pintype "bidirectional"))
      (node (ref "IC8") (pin "18") (pinfunction "I/O4_18") (pintype "bidirectional"))
      (node (ref "JP4") (pin "13") (pinfunction "13_13") (pintype "passive"))
      (node (ref "JP6") (pin "13") (pinfunction "13_13") (pintype "passive"))
    )
    (net (code "118") (name "/B0_D5") (class "Default")
      (node (ref "IC2") (pin "19") (pinfunction "I/O5_19") (pintype "bidirectional"))
      (node (ref "IC6") (pin "19") (pinfunction "I/O5_19") (pintype "bidirectional"))
      (node (ref "IC7") (pin "19") (pinfunction "I/O5_19") (pintype "bidirectional"))
      (node (ref "IC8") (pin "19") (pinfunction "I/O5_19") (pintype "bidirectional"))
      (node (ref "JP4") (pin "15") (pinfunction "15_15") (pintype "passive"))
      (node (ref "JP6") (pin "15") (pinfunction "15_15") (pintype "passive"))
    )
    (net (code "119") (name "/B0_D6") (class "Default")
      (node (ref "IC2") (pin "20") (pinfunction "I/O6_20") (pintype "bidirectional"))
      (node (ref "IC6") (pin "20") (pinfunction "I/O6_20") (pintype "bidirectional"))
      (node (ref "IC7") (pin "20") (pinfunction "I/O6_20") (pintype "bidirectional"))
      (node (ref "IC8") (pin "20") (pinfunction "I/O6_20") (pintype "bidirectional"))
      (node (ref "JP4") (pin "17") (pinfunction "17_17") (pintype "passive"))
      (node (ref "JP6") (pin "17") (pinfunction "17_17") (pintype "passive"))
    )
    (net (code "120") (name "/B0_D7") (class "Default")
      (node (ref "IC2") (pin "21") (pinfunction "I/O7_21") (pintype "bidirectional"))
      (node (ref "IC6") (pin "21") (pinfunction "I/O7_21") (pintype "bidirectional"))
      (node (ref "IC7") (pin "21") (pinfunction "I/O7_21") (pintype "bidirectional"))
      (node (ref "IC8") (pin "21") (pinfunction "I/O7_21") (pintype "bidirectional"))
      (node (ref "JP4") (pin "19") (pinfunction "19_19") (pintype "passive"))
      (node (ref "JP6") (pin "19") (pinfunction "19_19") (pintype "passive"))
    )
    (net (code "121") (name "/B1_A0") (class "Default")
      (node (ref "IC1") (pin "12") (pinfunction "A0_12") (pintype "bidirectional"))
      (node (ref "IC3") (pin "12") (pinfunction "A0_12") (pintype "bidirectional"))
      (node (ref "IC4") (pin "12") (pinfunction "A0_12") (pintype "bidirectional"))
      (node (ref "IC5") (pin "12") (pinfunction "A0_12") (pintype "bidirectional"))
      (node (ref "JP3") (pin "5") (pinfunction "5_5") (pintype "passive"))
      (node (ref "JP5") (pin "5") (pinfunction "5_5") (pintype "passive"))
      (node (ref "R33") (pin "1") (pinfunction "1_1") (pintype "bidirectional"))
    )
    (net (code "122") (name "/B1_A1") (class "Default")
      (node (ref "IC1") (pin "11") (pinfunction "A1_11") (pintype "bidirectional"))
      (node (ref "IC3") (pin "11") (pinfunction "A1_11") (pintype "bidirectional"))
      (node (ref "IC4") (pin "11") (pinfunction "A1_11") (pintype "bidirectional"))
      (node (ref "IC5") (pin "11") (pinfunction "A1_11") (pintype "bidirectional"))
      (node (ref "JP3") (pin "7") (pinfunction "7_7") (pintype "passive"))
      (node (ref "JP5") (pin "7") (pinfunction "7_7") (pintype "passive"))
      (node (ref "R34") (pin "1") (pinfunction "1_1") (pintype "bidirectional"))
    )
    (net (code "123") (name "/B1_A2") (class "Default")
      (node (ref "IC1") (pin "10") (pinfunction "A2_10") (pintype "bidirectional"))
      (node (ref "IC3") (pin "10") (pinfunction "A2_10") (pintype "bidirectional"))
      (node (ref "IC4") (pin "10") (pinfunction "A2_10") (pintype "bidirectional"))
      (node (ref "IC5") (pin "10") (pinfunction "A2_10") (pintype "bidirectional"))
      (node (ref "JP3") (pin "9") (pinfunction "9_9") (pintype "passive"))
      (node (ref "JP5") (pin "9") (pinfunction "9_9") (pintype "passive"))
      (node (ref "R35") (pin "1") (pinfunction "1_1") (pintype "bidirectional"))
    )
    (net (code "124") (name "/B1_A3") (class "Default")
      (node (ref "IC1") (pin "9") (pinfunction "A3_9") (pintype "bidirectional"))
      (node (ref "IC3") (pin "9") (pinfunction "A3_9") (pintype "bidirectional"))
      (node (ref "IC4") (pin "9") (pinfunction "A3_9") (pintype "bidirectional"))
      (node (ref "IC5") (pin "9") (pinfunction "A3_9") (pintype "bidirectional"))
      (node (ref "JP3") (pin "11") (pinfunction "11_11") (pintype "passive"))
      (node (ref "JP5") (pin "11") (pinfunction "11_11") (pintype "passive"))
      (node (ref "R36") (pin "1") (pinfunction "1_1") (pintype "bidirectional"))
    )
    (net (code "125") (name "/B1_A4") (class "Default")
      (node (ref "IC1") (pin "8") (pinfunction "A4_8") (pintype "bidirectional"))
      (node (ref "IC3") (pin "8") (pinfunction "A4_8") (pintype "bidirectional"))
      (node (ref "IC4") (pin "8") (pinfunction "A4_8") (pintype "bidirectional"))
      (node (ref "IC5") (pin "8") (pinfunction "A4_8") (pintype "bidirectional"))
      (node (ref "JP3") (pin "13") (pinfunction "13_13") (pintype "passive"))
      (node (ref "JP5") (pin "13") (pinfunction "13_13") (pintype "passive"))
      (node (ref "R37") (pin "1") (pinfunction "1_1") (pintype "bidirectional"))
    )
    (net (code "126") (name "/B1_A5") (class "Default")
      (node (ref "IC1") (pin "7") (pinfunction "A5_7") (pintype "bidirectional"))
      (node (ref "IC3") (pin "7") (pinfunction "A5_7") (pintype "bidirectional"))
      (node (ref "IC4") (pin "7") (pinfunction "A5_7") (pintype "bidirectional"))
      (node (ref "IC5") (pin "7") (pinfunction "A5_7") (pintype "bidirectional"))
      (node (ref "JP3") (pin "15") (pinfunction "15_15") (pintype "passive"))
      (node (ref "JP5") (pin "15") (pinfunction "15_15") (pintype "passive"))
      (node (ref "R38") (pin "1") (pinfunction "1_1") (pintype "bidirectional"))
    )
    (net (code "127") (name "/B1_A6") (class "Default")
      (node (ref "IC1") (pin "6") (pinfunction "A6_6") (pintype "bidirectional"))
      (node (ref "IC3") (pin "6") (pinfunction "A6_6") (pintype "bidirectional"))
      (node (ref "IC4") (pin "6") (pinfunction "A6_6") (pintype "bidirectional"))
      (node (ref "IC5") (pin "6") (pinfunction "A6_6") (pintype "bidirectional"))
      (node (ref "JP3") (pin "17") (pinfunction "17_17") (pintype "passive"))
      (node (ref "JP5") (pin "17") (pinfunction "17_17") (pintype "passive"))
      (node (ref "R39") (pin "1") (pinfunction "1_1") (pintype "bidirectional"))
    )
    (net (code "128") (name "/B1_A7") (class "Default")
      (node (ref "IC1") (pin "5") (pinfunction "A7_5") (pintype "bidirectional"))
      (node (ref "IC3") (pin "5") (pinfunction "A7_5") (pintype "bidirectional"))
      (node (ref "IC4") (pin "5") (pinfunction "A7_5") (pintype "bidirectional"))
      (node (ref "IC5") (pin "5") (pinfunction "A7_5") (pintype "bidirectional"))
      (node (ref "JP3") (pin "19") (pinfunction "19_19") (pintype "passive"))
      (node (ref "JP5") (pin "19") (pinfunction "19_19") (pintype "passive"))
      (node (ref "R40") (pin "1") (pinfunction "1_1") (pintype "bidirectional"))
    )
    (net (code "129") (name "/B1_A8") (class "Default")
      (node (ref "IC1") (pin "27") (pinfunction "A8_27") (pintype "bidirectional"))
      (node (ref "IC3") (pin "27") (pinfunction "A8_27") (pintype "bidirectional"))
      (node (ref "IC4") (pin "27") (pinfunction "A8_27") (pintype "bidirectional"))
      (node (ref "IC5") (pin "27") (pinfunction "A8_27") (pintype "bidirectional"))
      (node (ref "JP3") (pin "21") (pinfunction "21_21") (pintype "passive"))
      (node (ref "JP5") (pin "21") (pinfunction "21_21") (pintype "passive"))
      (node (ref "R41") (pin "1") (pinfunction "1_1") (pintype "bidirectional"))
    )
    (net (code "130") (name "/B1_A9") (class "Default")
      (node (ref "IC1") (pin "26") (pinfunction "A9_26") (pintype "bidirectional"))
      (node (ref "IC3") (pin "26") (pinfunction "A9_26") (pintype "bidirectional"))
      (node (ref "IC4") (pin "26") (pinfunction "A9_26") (pintype "bidirectional"))
      (node (ref "IC5") (pin "26") (pinfunction "A9_26") (pintype "bidirectional"))
      (node (ref "JP3") (pin "23") (pinfunction "23_23") (pintype "passive"))
      (node (ref "JP5") (pin "23") (pinfunction "23_23") (pintype "passive"))
      (node (ref "R42") (pin "1") (pinfunction "1_1") (pintype "bidirectional"))
    )
    (net (code "131") (name "/B1_A10") (class "Default")
      (node (ref "IC1") (pin "23") (pinfunction "A10_23") (pintype "bidirectional"))
      (node (ref "IC3") (pin "23") (pinfunction "A10_23") (pintype "bidirectional"))
      (node (ref "IC4") (pin "23") (pinfunction "A10_23") (pintype "bidirectional"))
      (node (ref "IC5") (pin "23") (pinfunction "A10_23") (pintype "bidirectional"))
      (node (ref "JP3") (pin "25") (pinfunction "25_25") (pintype "passive"))
      (node (ref "JP5") (pin "25") (pinfunction "25_25") (pintype "passive"))
      (node (ref "R43") (pin "1") (pinfunction "1_1") (pintype "bidirectional"))
    )
    (net (code "132") (name "/B1_A11") (class "Default")
      (node (ref "IC1") (pin "25") (pinfunction "A11_25") (pintype "bidirectional"))
      (node (ref "IC3") (pin "25") (pinfunction "A11_25") (pintype "bidirectional"))
      (node (ref "IC4") (pin "25") (pinfunction "A11_25") (pintype "bidirectional"))
      (node (ref "IC5") (pin "25") (pinfunction "A11_25") (pintype "bidirectional"))
      (node (ref "JP3") (pin "27") (pinfunction "27_27") (pintype "passive"))
      (node (ref "JP5") (pin "27") (pinfunction "27_27") (pintype "passive"))
      (node (ref "R44") (pin "1") (pinfunction "1_1") (pintype "bidirectional"))
    )
    (net (code "133") (name "/B1_A12") (class "Default")
      (node (ref "IC1") (pin "4") (pinfunction "A12_4") (pintype "bidirectional"))
      (node (ref "IC3") (pin "4") (pinfunction "A12_4") (pintype "bidirectional"))
      (node (ref "IC4") (pin "4") (pinfunction "A12_4") (pintype "bidirectional"))
      (node (ref "IC5") (pin "4") (pinfunction "A12_4") (pintype "bidirectional"))
      (node (ref "JP3") (pin "29") (pinfunction "29_29") (pintype "passive"))
      (node (ref "JP5") (pin "29") (pinfunction "29_29") (pintype "passive"))
      (node (ref "R45") (pin "1") (pinfunction "1_1") (pintype "bidirectional"))
    )
    (net (code "134") (name "/B1_A13") (class "Default")
      (node (ref "IC1") (pin "28") (pinfunction "A13_28") (pintype "bidirectional"))
      (node (ref "IC3") (pin "28") (pinfunction "A13_28") (pintype "bidirectional"))
      (node (ref "IC4") (pin "28") (pinfunction "A13_28") (pintype "bidirectional"))
      (node (ref "IC5") (pin "28") (pinfunction "A13_28") (pintype "bidirectional"))
      (node (ref "JP3") (pin "31") (pinfunction "31_31") (pintype "passive"))
      (node (ref "JP5") (pin "31") (pinfunction "31_31") (pintype "passive"))
      (node (ref "R46") (pin "1") (pinfunction "1_1") (pintype "bidirectional"))
    )
    (net (code "135") (name "/B1_A14") (class "Default")
      (node (ref "IC1") (pin "3") (pinfunction "A14_3") (pintype "bidirectional"))
      (node (ref "IC3") (pin "3") (pinfunction "A14_3") (pintype "bidirectional"))
      (node (ref "IC4") (pin "3") (pinfunction "A14_3") (pintype "bidirectional"))
      (node (ref "IC5") (pin "3") (pinfunction "A14_3") (pintype "bidirectional"))
      (node (ref "JP3") (pin "33") (pinfunction "33_33") (pintype "passive"))
      (node (ref "JP5") (pin "33") (pinfunction "33_33") (pintype "passive"))
      (node (ref "R47") (pin "1") (pinfunction "1_1") (pintype "bidirectional"))
    )
    (net (code "136") (name "/B1_A15") (class "Default")
      (node (ref "IC1") (pin "31") (pinfunction "A15_31") (pintype "bidirectional"))
      (node (ref "IC3") (pin "31") (pinfunction "A15_31") (pintype "bidirectional"))
      (node (ref "IC4") (pin "31") (pinfunction "A15_31") (pintype "bidirectional"))
      (node (ref "IC5") (pin "31") (pinfunction "A15_31") (pintype "bidirectional"))
      (node (ref "JP3") (pin "35") (pinfunction "35_35") (pintype "passive"))
      (node (ref "JP5") (pin "35") (pinfunction "35_35") (pintype "passive"))
      (node (ref "R49") (pin "1") (pinfunction "1_1") (pintype "bidirectional"))
    )
    (net (code "137") (name "/B1_A16") (class "Default")
      (node (ref "IC1") (pin "2") (pinfunction "A16_2") (pintype "bidirectional"))
      (node (ref "IC3") (pin "2") (pinfunction "A16_2") (pintype "bidirectional"))
      (node (ref "IC4") (pin "2") (pinfunction "A16_2") (pintype "bidirectional"))
      (node (ref "IC5") (pin "2") (pinfunction "A16_2") (pintype "bidirectional"))
      (node (ref "JP3") (pin "6") (pinfunction "6_6") (pintype "passive"))
      (node (ref "JP5") (pin "6") (pinfunction "6_6") (pintype "passive"))
      (node (ref "R48") (pin "1") (pinfunction "1_1") (pintype "bidirectional"))
    )
    (net (code "138") (name "/B1_A17") (class "Default")
      (node (ref "IC1") (pin "1") (pinfunction "A17_1") (pintype "bidirectional"))
      (node (ref "IC3") (pin "1") (pinfunction "A17_1") (pintype "bidirectional"))
      (node (ref "IC4") (pin "1") (pinfunction "A17_1") (pintype "bidirectional"))
      (node (ref "IC5") (pin "1") (pinfunction "A17_1") (pintype "bidirectional"))
      (node (ref "JP3") (pin "8") (pinfunction "8_8") (pintype "passive"))
      (node (ref "JP5") (pin "8") (pinfunction "8_8") (pintype "passive"))
      (node (ref "R50") (pin "1") (pinfunction "1_1") (pintype "bidirectional"))
    )
    (net (code "139") (name "/B1_A18") (class "Default")
      (node (ref "IC1") (pin "30") (pinfunction "A18_30") (pintype "bidirectional"))
      (node (ref "IC3") (pin "30") (pinfunction "A18_30") (pintype "bidirectional"))
      (node (ref "IC4") (pin "30") (pinfunction "A18_30") (pintype "bidirectional"))
      (node (ref "IC5") (pin "30") (pinfunction "A18_30") (pintype "bidirectional"))
      (node (ref "JP3") (pin "10") (pinfunction "10_10") (pintype "passive"))
      (node (ref "JP5") (pin "10") (pinfunction "10_10") (pintype "passive"))
      (node (ref "R51") (pin "1") (pinfunction "1_1") (pintype "bidirectional"))
    )
    (net (code "140") (name "/B1_A19") (class "Default")
      (node (ref "IC10") (pin "1") (pinfunction "A_1") (pintype "bidirectional"))
      (node (ref "JP3") (pin "12") (pinfunction "12_12") (pintype "passive"))
      (node (ref "JP5") (pin "12") (pinfunction "12_12") (pintype "passive"))
      (node (ref "R52") (pin "1") (pinfunction "1_1") (pintype "bidirectional"))
    )
    (net (code "141") (name "/B1_A20") (class "Default")
      (node (ref "IC10") (pin "2") (pinfunction "B_2") (pintype "bidirectional"))
      (node (ref "JP3") (pin "14") (pinfunction "14_14") (pintype "passive"))
      (node (ref "JP5") (pin "14") (pinfunction "14_14") (pintype "passive"))
      (node (ref "R53") (pin "1") (pinfunction "1_1") (pintype "bidirectional"))
    )
    (net (code "142") (name "/B1_A21") (class "Default")
      (node (ref "JP3") (pin "16") (pinfunction "16_16") (pintype "passive"))
      (node (ref "JP5") (pin "16") (pinfunction "16_16") (pintype "passive"))
      (node (ref "R54") (pin "1") (pinfunction "1_1") (pintype "bidirectional"))
    )
    (net (code "143") (name "/B1_A22") (class "Default")
      (node (ref "JP3") (pin "18") (pinfunction "18_18") (pintype "passive"))
      (node (ref "JP5") (pin "18") (pinfunction "18_18") (pintype "passive"))
      (node (ref "R55") (pin "1") (pinfunction "1_1") (pintype "bidirectional"))
    )
    (net (code "144") (name "/B1_A23") (class "Default")
      (node (ref "JP3") (pin "20") (pinfunction "20_20") (pintype "passive"))
      (node (ref "JP5") (pin "20") (pinfunction "20_20") (pintype "passive"))
      (node (ref "R56") (pin "1") (pinfunction "1_1") (pintype "bidirectional"))
    )
    (net (code "145") (name "/B1_A24") (class "Default")
      (node (ref "JP3") (pin "22") (pinfunction "22_22") (pintype "passive"))
      (node (ref "JP5") (pin "22") (pinfunction "22_22") (pintype "passive"))
      (node (ref "R58") (pin "1") (pinfunction "1_1") (pintype "bidirectional"))
    )
    (net (code "146") (name "/B1_A25") (class "Default")
      (node (ref "JP3") (pin "24") (pinfunction "24_24") (pintype "passive"))
      (node (ref "JP5") (pin "24") (pinfunction "24_24") (pintype "passive"))
      (node (ref "R57") (pin "1") (pinfunction "1_1") (pintype "bidirectional"))
    )
    (net (code "147") (name "/B1_A26") (class "Default")
      (node (ref "JP3") (pin "26") (pinfunction "26_26") (pintype "passive"))
      (node (ref "JP5") (pin "26") (pinfunction "26_26") (pintype "passive"))
      (node (ref "R59") (pin "1") (pinfunction "1_1") (pintype "bidirectional"))
    )
    (net (code "148") (name "/B1_A27") (class "Default")
      (node (ref "JP3") (pin "28") (pinfunction "28_28") (pintype "passive"))
      (node (ref "JP5") (pin "28") (pinfunction "28_28") (pintype "passive"))
      (node (ref "R60") (pin "1") (pinfunction "1_1") (pintype "bidirectional"))
    )
    (net (code "149") (name "/B1_A28") (class "Default")
      (node (ref "JP3") (pin "30") (pinfunction "30_30") (pintype "passive"))
      (node (ref "JP5") (pin "30") (pinfunction "30_30") (pintype "passive"))
      (node (ref "R61") (pin "1") (pinfunction "1_1") (pintype "bidirectional"))
    )
    (net (code "150") (name "/B1_A29") (class "Default")
      (node (ref "JP3") (pin "32") (pinfunction "32_32") (pintype "passive"))
      (node (ref "JP5") (pin "32") (pinfunction "32_32") (pintype "passive"))
      (node (ref "R62") (pin "1") (pinfunction "1_1") (pintype "bidirectional"))
    )
    (net (code "151") (name "/B1_A30") (class "Default")
      (node (ref "JP3") (pin "34") (pinfunction "34_34") (pintype "passive"))
      (node (ref "JP5") (pin "34") (pinfunction "34_34") (pintype "passive"))
      (node (ref "R63") (pin "1") (pinfunction "1_1") (pintype "bidirectional"))
    )
    (net (code "152") (name "/B1_A31") (class "Default")
      (node (ref "JP3") (pin "36") (pinfunction "36_36") (pintype "passive"))
      (node (ref "JP5") (pin "36") (pinfunction "36_36") (pintype "passive"))
      (node (ref "R64") (pin "1") (pinfunction "1_1") (pintype "bidirectional"))
    )
    (net (code "153") (name "/B1_D0") (class "Default")
      (node (ref "IC1") (pin "13") (pinfunction "I/O0_13") (pintype "bidirectional"))
      (node (ref "IC3") (pin "13") (pinfunction "I/O0_13") (pintype "bidirectional"))
      (node (ref "IC4") (pin "13") (pinfunction "I/O0_13") (pintype "bidirectional"))
      (node (ref "IC5") (pin "13") (pinfunction "I/O0_13") (pintype "bidirectional"))
      (node (ref "JP4") (pin "6") (pinfunction "6_6") (pintype "passive"))
      (node (ref "JP6") (pin "6") (pinfunction "6_6") (pintype "passive"))
    )
    (net (code "154") (name "/B1_D1") (class "Default")
      (node (ref "IC1") (pin "14") (pinfunction "I/O1_14") (pintype "bidirectional"))
      (node (ref "IC3") (pin "14") (pinfunction "I/O1_14") (pintype "bidirectional"))
      (node (ref "IC4") (pin "14") (pinfunction "I/O1_14") (pintype "bidirectional"))
      (node (ref "IC5") (pin "14") (pinfunction "I/O1_14") (pintype "bidirectional"))
      (node (ref "JP4") (pin "8") (pinfunction "8_8") (pintype "passive"))
      (node (ref "JP6") (pin "8") (pinfunction "8_8") (pintype "passive"))
    )
    (net (code "155") (name "/B1_D2") (class "Default")
      (node (ref "IC1") (pin "15") (pinfunction "I/O2_15") (pintype "bidirectional"))
      (node (ref "IC3") (pin "15") (pinfunction "I/O2_15") (pintype "bidirectional"))
      (node (ref "IC4") (pin "15") (pinfunction "I/O2_15") (pintype "bidirectional"))
      (node (ref "IC5") (pin "15") (pinfunction "I/O2_15") (pintype "bidirectional"))
      (node (ref "JP4") (pin "10") (pinfunction "10_10") (pintype "passive"))
      (node (ref "JP6") (pin "10") (pinfunction "10_10") (pintype "passive"))
    )
    (net (code "156") (name "/B1_D3") (class "Default")
      (node (ref "IC1") (pin "17") (pinfunction "I/O3_17") (pintype "bidirectional"))
      (node (ref "IC3") (pin "17") (pinfunction "I/O3_17") (pintype "bidirectional"))
      (node (ref "IC4") (pin "17") (pinfunction "I/O3_17") (pintype "bidirectional"))
      (node (ref "IC5") (pin "17") (pinfunction "I/O3_17") (pintype "bidirectional"))
      (node (ref "JP4") (pin "12") (pinfunction "12_12") (pintype "passive"))
      (node (ref "JP6") (pin "12") (pinfunction "12_12") (pintype "passive"))
    )
    (net (code "157") (name "/B1_D4") (class "Default")
      (node (ref "IC1") (pin "18") (pinfunction "I/O4_18") (pintype "bidirectional"))
      (node (ref "IC3") (pin "18") (pinfunction "I/O4_18") (pintype "bidirectional"))
      (node (ref "IC4") (pin "18") (pinfunction "I/O4_18") (pintype "bidirectional"))
      (node (ref "IC5") (pin "18") (pinfunction "I/O4_18") (pintype "bidirectional"))
      (node (ref "JP4") (pin "14") (pinfunction "14_14") (pintype "passive"))
      (node (ref "JP6") (pin "14") (pinfunction "14_14") (pintype "passive"))
    )
    (net (code "158") (name "/B1_D5") (class "Default")
      (node (ref "IC1") (pin "19") (pinfunction "I/O5_19") (pintype "bidirectional"))
      (node (ref "IC3") (pin "19") (pinfunction "I/O5_19") (pintype "bidirectional"))
      (node (ref "IC4") (pin "19") (pinfunction "I/O5_19") (pintype "bidirectional"))
      (node (ref "IC5") (pin "19") (pinfunction "I/O5_19") (pintype "bidirectional"))
      (node (ref "JP4") (pin "16") (pinfunction "16_16") (pintype "passive"))
      (node (ref "JP6") (pin "16") (pinfunction "16_16") (pintype "passive"))
    )
    (net (code "159") (name "/B1_D6") (class "Default")
      (node (ref "IC1") (pin "20") (pinfunction "I/O6_20") (pintype "bidirectional"))
      (node (ref "IC3") (pin "20") (pinfunction "I/O6_20") (pintype "bidirectional"))
      (node (ref "IC4") (pin "20") (pinfunction "I/O6_20") (pintype "bidirectional"))
      (node (ref "IC5") (pin "20") (pinfunction "I/O6_20") (pintype "bidirectional"))
      (node (ref "JP4") (pin "18") (pinfunction "18_18") (pintype "passive"))
      (node (ref "JP6") (pin "18") (pinfunction "18_18") (pintype "passive"))
    )
    (net (code "160") (name "/B1_D7") (class "Default")
      (node (ref "IC1") (pin "21") (pinfunction "I/O7_21") (pintype "bidirectional"))
      (node (ref "IC3") (pin "21") (pinfunction "I/O7_21") (pintype "bidirectional"))
      (node (ref "IC4") (pin "21") (pinfunction "I/O7_21") (pintype "bidirectional"))
      (node (ref "IC5") (pin "21") (pinfunction "I/O7_21") (pintype "bidirectional"))
      (node (ref "JP4") (pin "20") (pinfunction "20_20") (pintype "passive"))
      (node (ref "JP6") (pin "20") (pinfunction "20_20") (pintype "passive"))
    )
    (net (code "161") (name "/CE0") (class "Default")
      (node (ref "IC8") (pin "22") (pinfunction "~{CE}_22") (pintype "bidirectional"))
      (node (ref "IC9") (pin "15") (pinfunction "Y0_15") (pintype "bidirectional"))
    )
    (net (code "162") (name "/CE1") (class "Default")
      (node (ref "IC2") (pin "22") (pinfunction "~{CE}_22") (pintype "bidirectional"))
      (node (ref "IC9") (pin "14") (pinfunction "Y1_14") (pintype "bidirectional"))
    )
    (net (code "163") (name "/CE2") (class "Default")
      (node (ref "IC6") (pin "22") (pinfunction "~{CE}_22") (pintype "bidirectional"))
      (node (ref "IC9") (pin "13") (pinfunction "Y2_13") (pintype "bidirectional"))
    )
    (net (code "164") (name "/CE3") (class "Default")
      (node (ref "IC7") (pin "22") (pinfunction "~{CE}_22") (pintype "bidirectional"))
      (node (ref "IC9") (pin "12") (pinfunction "Y3_12") (pintype "bidirectional"))
    )
    (net (code "165") (name "/CE4") (class "Default")
      (node (ref "IC10") (pin "15") (pinfunction "Y0_15") (pintype "bidirectional"))
      (node (ref "IC5") (pin "22") (pinfunction "~{CE}_22") (pintype "bidirectional"))
    )
    (net (code "166") (name "/CE5") (class "Default")
      (node (ref "IC1") (pin "22") (pinfunction "~{CE}_22") (pintype "bidirectional"))
      (node (ref "IC10") (pin "14") (pinfunction "Y1_14") (pintype "bidirectional"))
    )
    (net (code "167") (name "/CE6") (class "Default")
      (node (ref "IC10") (pin "13") (pinfunction "Y2_13") (pintype "bidirectional"))
      (node (ref "IC3") (pin "22") (pinfunction "~{CE}_22") (pintype "bidirectional"))
    )
    (net (code "168") (name "/CE7") (class "Default")
      (node (ref "IC10") (pin "12") (pinfunction "Y3_12") (pintype "bidirectional"))
      (node (ref "IC4") (pin "22") (pinfunction "~{CE}_22") (pintype "bidirectional"))
    )
    (net (code "173") (name "/OE") (class "Default")
      (node (ref "IC1") (pin "24") (pinfunction "~{OE}_24") (pintype "bidirectional"))
      (node (ref "IC2") (pin "24") (pinfunction "~{OE}_24") (pintype "bidirectional"))
      (node (ref "IC3") (pin "24") (pinfunction "~{OE}_24") (pintype "bidirectional"))
      (node (ref "IC4") (pin "24") (pinfunction "~{OE}_24") (pintype "bidirectional"))
      (node (ref "IC5") (pin "24") (pinfunction "~{OE}_24") (pintype "bidirectional"))
      (node (ref "IC6") (pin "24") (pinfunction "~{OE}_24") (pintype "bidirectional"))
      (node (ref "IC7") (pin "24") (pinfunction "~{OE}_24") (pintype "bidirectional"))
      (node (ref "IC8") (pin "24") (pinfunction "~{OE}_24") (pintype "bidirectional"))
    )
    (net (code "174") (name "/WE") (class "Default")
      (node (ref "IC1") (pin "29") (pinfunction "~{WE}_29") (pintype "bidirectional"))
      (node (ref "IC2") (pin "29") (pinfunction "~{WE}_29") (pintype "bidirectional"))
      (node (ref "IC3") (pin "29") (pinfunction "~{WE}_29") (pintype "bidirectional"))
      (node (ref "IC4") (pin "29") (pinfunction "~{WE}_29") (pintype "bidirectional"))
      (node (ref "IC5") (pin "29") (pinfunction "~{WE}_29") (pintype "bidirectional"))
      (node (ref "IC6") (pin "29") (pinfunction "~{WE}_29") (pintype "bidirectional"))
      (node (ref "IC7") (pin "29") (pinfunction "~{WE}_29") (pintype "bidirectional"))
      (node (ref "IC8") (pin "29") (pinfunction "~{WE}_29") (pintype "bidirectional"))
    )
    (net (code "175") (name "GND") (class "Default")
      (node (ref "C1") (pin "1") (pinfunction "1_1") (pintype "bidirectional"))
      (node (ref "C10") (pin "1") (pinfunction "1_1") (pintype "bidirectional"))
      (node (ref "C2") (pin "1") (pinfunction "1_1") (pintype "bidirectional"))
      (node (ref "C3") (pin "1") (pinfunction "1_1") (pintype "bidirectional"))
      (node (ref "C4") (pin "1") (pinfunction "1_1") (pintype "bidirectional"))
      (node (ref "C5") (pin "1") (pinfunction "1_1") (pintype "bidirectional"))
      (node (ref "C6") (pin "1") (pinfunction "1_1") (pintype "bidirectional"))
      (node (ref "C7") (pin "1") (pinfunction "1_1") (pintype "bidirectional"))
      (node (ref "C8") (pin "1") (pinfunction "1_1") (pintype "bidirectional"))
      (node (ref "C9") (pin "1") (pinfunction "1_1") (pintype "bidirectional"))
      (node (ref "IC1") (pin "16") (pinfunction "GND_16") (pintype "bidirectional"))
      (node (ref "IC10") (pin "3") (pinfunction "C_3") (pintype "bidirectional"))
      (node (ref "IC10") (pin "4") (pinfunction "~{G2A}_4") (pintype "bidirectional"))
      (node (ref "IC10") (pin "5") (pinfunction "~{G2B}_5") (pintype "bidirectional"))
      (node (ref "IC10") (pin "8") (pinfunction "GND_8") (pintype "bidirectional"))
      (node (ref "IC2") (pin "16") (pinfunction "GND_16") (pintype "bidirectional"))
      (node (ref "IC3") (pin "16") (pinfunction "GND_16") (pintype "bidirectional"))
      (node (ref "IC4") (pin "16") (pinfunction "GND_16") (pintype "bidirectional"))
      (node (ref "IC5") (pin "16") (pinfunction "GND_16") (pintype "bidirectional"))
      (node (ref "IC6") (pin "16") (pinfunction "GND_16") (pintype "bidirectional"))
      (node (ref "IC7") (pin "16") (pinfunction "GND_16") (pintype "bidirectional"))
      (node (ref "IC8") (pin "16") (pinfunction "GND_16") (pintype "bidirectional"))
      (node (ref "IC9") (pin "3") (pinfunction "C_3") (pintype "bidirectional"))
      (node (ref "IC9") (pin "4") (pinfunction "~{G2A}_4") (pintype "bidirectional"))
      (node (ref "IC9") (pin "5") (pinfunction "~{G2B}_5") (pintype "bidirectional"))
      (node (ref "IC9") (pin "8") (pinfunction "GND_8") (pintype "bidirectional"))
      (node (ref "JP1") (pin "3") (pinfunction "3_3") (pintype "passive"))
      (node (ref "JP1") (pin "37") (pinfunction "37_37") (pintype "passive"))
      (node (ref "JP1") (pin "38") (pinfunction "38_38") (pintype "passive"))
      (node (ref "JP1") (pin "4") (pinfunction "4_4") (pintype "passive"))
      (node (ref "JP2") (pin "3") (pinfunction "3_3") (pintype "passive"))
      (node (ref "JP2") (pin "37") (pinfunction "37_37") (pintype "passive"))
      (node (ref "JP2") (pin "38") (pinfunction "38_38") (pintype "passive"))
      (node (ref "JP2") (pin "4") (pinfunction "4_4") (pintype "passive"))
      (node (ref "JP3") (pin "3") (pinfunction "3_3") (pintype "passive"))
      (node (ref "JP3") (pin "37") (pinfunction "37_37") (pintype "passive"))
      (node (ref "JP3") (pin "38") (pinfunction "38_38") (pintype "passive"))
      (node (ref "JP3") (pin "4") (pinfunction "4_4") (pintype "passive"))
      (node (ref "JP4") (pin "3") (pinfunction "3_3") (pintype "passive"))
      (node (ref "JP4") (pin "37") (pinfunction "37_37") (pintype "passive"))
      (node (ref "JP4") (pin "38") (pinfunction "38_38") (pintype "passive"))
      (node (ref "JP4") (pin "4") (pinfunction "4_4") (pintype "passive"))
      (node (ref "JP5") (pin "3") (pinfunction "3_3") (pintype "passive"))
      (node (ref "JP5") (pin "37") (pinfunction "37_37") (pintype "passive"))
      (node (ref "JP5") (pin "38") (pinfunction "38_38") (pintype "passive"))
      (node (ref "JP5") (pin "4") (pinfunction "4_4") (pintype "passive"))
      (node (ref "JP6") (pin "3") (pinfunction "3_3") (pintype "passive"))
      (node (ref "JP6") (pin "37") (pinfunction "37_37") (pintype "passive"))
      (node (ref "JP6") (pin "38") (pinfunction "38_38") (pintype "passive"))
      (node (ref "JP6") (pin "4") (pinfunction "4_4") (pintype "passive"))
      (node (ref "R1") (pin "2") (pinfunction "2_2") (pintype "bidirectional"))
      (node (ref "R10") (pin "2") (pinfunction "2_2") (pintype "bidirectional"))
      (node (ref "R11") (pin "2") (pinfunction "2_2") (pintype "bidirectional"))
      (node (ref "R12") (pin "2") (pinfunction "2_2") (pintype "bidirectional"))
      (node (ref "R13") (pin "2") (pinfunction "2_2") (pintype "bidirectional"))
      (node (ref "R14") (pin "2") (pinfunction "2_2") (pintype "bidirectional"))
      (node (ref "R15") (pin "2") (pinfunction "2_2") (pintype "bidirectional"))
      (node (ref "R16") (pin "2") (pinfunction "2_2") (pintype "bidirectional"))
      (node (ref "R17") (pin "2") (pinfunction "2_2") (pintype "bidirectional"))
      (node (ref "R18") (pin "2") (pinfunction "2_2") (pintype "bidirectional"))
      (node (ref "R19") (pin "2") (pinfunction "2_2") (pintype "bidirectional"))
      (node (ref "R2") (pin "2") (pinfunction "2_2") (pintype "bidirectional"))
      (node (ref "R20") (pin "2") (pinfunction "2_2") (pintype "bidirectional"))
      (node (ref "R21") (pin "2") (pinfunction "2_2") (pintype "bidirectional"))
      (node (ref "R22") (pin "2") (pinfunction "2_2") (pintype "bidirectional"))
      (node (ref "R23") (pin "2") (pinfunction "2_2") (pintype "bidirectional"))
      (node (ref "R24") (pin "2") (pinfunction "2_2") (pintype "bidirectional"))
      (node (ref "R25") (pin "2") (pinfunction "2_2") (pintype "bidirectional"))
      (node (ref "R26") (pin "2") (pinfunction "2_2") (pintype "bidirectional"))
      (node (ref "R27") (pin "2") (pinfunction "2_2") (pintype "bidirectional"))
      (node (ref "R28") (pin "2") (pinfunction "2_2") (pintype "bidirectional"))
      (node (ref "R29") (pin "2") (pinfunction "2_2") (pintype "bidirectional"))
      (node (ref "R3") (pin "2") (pinfunction "2_2") (pintype "bidirectional"))
      (node (ref "R30") (pin "2") (pinfunction "2_2") (pintype "bidirectional"))
      (node (ref "R31") (pin "2") (pinfunction "2_2") (pintype "bidirectional"))
      (node (ref "R32") (pin "2") (pinfunction "2_2") (pintype "bidirectional"))
      (node (ref "R33") (pin "2") (pinfunction "2_2") (pintype "bidirectional"))
      (node (ref "R34") (pin "2") (pinfunction "2_2") (pintype "bidirectional"))
      (node (ref "R35") (pin "2") (pinfunction "2_2") (pintype "bidirectional"))
      (node (ref "R36") (pin "2") (pinfunction "2_2") (pintype "bidirectional"))
      (node (ref "R37") (pin "2") (pinfunction "2_2") (pintype "bidirectional"))
      (node (ref "R38") (pin "2") (pinfunction "2_2") (pintype "bidirectional"))
      (node (ref "R39") (pin "2") (pinfunction "2_2") (pintype "bidirectional"))
      (node (ref "R4") (pin "2") (pinfunction "2_2") (pintype "bidirectional"))
      (node (ref "R40") (pin "2") (pinfunction "2_2") (pintype "bidirectional"))
      (node (ref "R41") (pin "2") (pinfunction "2_2") (pintype "bidirectional"))
      (node (ref "R42") (pin "2") (pinfunction "2_2") (pintype "bidirectional"))
      (node (ref "R43") (pin "2") (pinfunction "2_2") (pintype "bidirectional"))
      (node (ref "R44") (pin "2") (pinfunction "2_2") (pintype "bidirectional"))
      (node (ref "R45") (pin "2") (pinfunction "2_2") (pintype "bidirectional"))
      (node (ref "R46") (pin "2") (pinfunction "2_2") (pintype "bidirectional"))
      (node (ref "R47") (pin "2") (pinfunction "2_2") (pintype "bidirectional"))
      (node (ref "R48") (pin "2") (pinfunction "2_2") (pintype "bidirectional"))
      (node (ref "R49") (pin "2") (pinfunction "2_2") (pintype "bidirectional"))
      (node (ref "R5") (pin "2") (pinfunction "2_2") (pintype "bidirectional"))
      (node (ref "R50") (pin "2") (pinfunction "2_2") (pintype "bidirectional"))
      (node (ref "R51") (pin "2") (pinfunction "2_2") (pintype "bidirectional"))
      (node (ref "R52") (pin "2") (pinfunction "2_2") (pintype "bidirectional"))
      (node (ref "R53") (pin "2") (pinfunction "2_2") (pintype "bidirectional"))
      (node (ref "R54") (pin "2") (pinfunction "2_2") (pintype "bidirectional"))
      (node (ref "R55") (pin "2") (pinfunction "2_2") (pintype "bidirectional"))
      (node (ref "R56") (pin "2") (pinfunction "2_2") (pintype "bidirectional"))
      (node (ref "R57") (pin "2") (pinfunction "2_2") (pintype "bidirectional"))
      (node (ref "R58") (pin "2") (pinfunction "2_2") (pintype "bidirectional"))
      (node (ref "R59") (pin "2") (pinfunction "2_2") (pintype "bidirectional"))
      (node (ref "R6") (pin "2") (pinfunction "2_2") (pintype "bidirectional"))
      (node (ref "R60") (pin "2") (pinfunction "2_2") (pintype "bidirectional"))
      (node (ref "R61") (pin "2") (pinfunction "2_2") (pintype "bidirectional"))
      (node (ref "R62") (pin "2") (pinfunction "2_2") (pintype "bidirectional"))
      (node (ref "R63") (pin "2") (pinfunction "2_2") (pintype "bidirectional"))
      (node (ref "R64") (pin "2") (pinfunction "2_2") (pintype "bidirectional"))
      (node (ref "R7") (pin "2") (pinfunction "2_2") (pintype "bidirectional"))
      (node (ref "R8") (pin "2") (pinfunction "2_2") (pintype "bidirectional"))
      (node (ref "R9") (pin "2") (pinfunction "2_2") (pintype "bidirectional"))
    )
    (net (code "176") (name "VCC") (class "Default")
      (node (ref "C1") (pin "2") (pinfunction "2_2") (pintype "bidirectional"))
      (node (ref "C10") (pin "2") (pinfunction "2_2") (pintype "bidirectional"))
      (node (ref "C2") (pin "2") (pinfunction "2_2") (pintype "bidirectional"))
      (node (ref "C3") (pin "2") (pinfunction "2_2") (pintype "bidirectional"))
      (node (ref "C4") (pin "2") (pinfunction "2_2") (pintype "bidirectional"))
      (node (ref "C5") (pin "2") (pinfunction "2_2") (pintype "bidirectional"))
      (node (ref "C6") (pin "2") (pinfunction "2_2") (pintype "bidirectional"))
      (node (ref "C7") (pin "2") (pinfunction "2_2") (pintype "bidirectional"))
      (node (ref "C8") (pin "2") (pinfunction "2_2") (pintype "bidirectional"))
      (node (ref "C9") (pin "2") (pinfunction "2_2") (pintype "bidirectional"))
      (node (ref "IC1") (pin "32") (pinfunction "VDD_32") (pintype "bidirectional"))
      (node (ref "IC10") (pin "16") (pinfunction "VCC_16") (pintype "bidirectional"))
      (node (ref "IC10") (pin "6") (pinfunction "G1_6") (pintype "bidirectional"))
      (node (ref "IC2") (pin "32") (pinfunction "VDD_32") (pintype "bidirectional"))
      (node (ref "IC3") (pin "32") (pinfunction "VDD_32") (pintype "bidirectional"))
      (node (ref "IC4") (pin "32") (pinfunction "VDD_32") (pintype "bidirectional"))
      (node (ref "IC5") (pin "32") (pinfunction "VDD_32") (pintype "bidirectional"))
      (node (ref "IC6") (pin "32") (pinfunction "VDD_32") (pintype "bidirectional"))
      (node (ref "IC7") (pin "32") (pinfunction "VDD_32") (pintype "bidirectional"))
      (node (ref "IC8") (pin "32") (pinfunction "VDD_32") (pintype "bidirectional"))
      (node (ref "IC9") (pin "16") (pinfunction "VCC_16") (pintype "bidirectional"))
      (node (ref "IC9") (pin "6") (pinfunction "G1_6") (pintype "bidirectional"))
      (node (ref "JP1") (pin "1") (pinfunction "1_1") (pintype "passive"))
      (node (ref "JP1") (pin "2") (pinfunction "2_2") (pintype "passive"))
      (node (ref "JP1") (pin "39") (pinfunction "39_39") (pintype "passive"))
      (node (ref "JP1") (pin "40") (pinfunction "40_40") (pintype "passive"))
      (node (ref "JP2") (pin "1") (pinfunction "1_1") (pintype "passive"))
      (node (ref "JP2") (pin "2") (pinfunction "2_2") (pintype "passive"))
      (node (ref "JP2") (pin "39") (pinfunction "39_39") (pintype "passive"))
      (node (ref "JP2") (pin "40") (pinfunction "40_40") (pintype "passive"))
      (node (ref "JP3") (pin "1") (pinfunction "1_1") (pintype "passive"))
      (node (ref "JP3") (pin "2") (pinfunction "2_2") (pintype "passive"))
      (node (ref "JP3") (pin "39") (pinfunction "39_39") (pintype "passive"))
      (node (ref "JP3") (pin "40") (pinfunction "40_40") (pintype "passive"))
      (node (ref "JP4") (pin "1") (pinfunction "1_1") (pintype "passive"))
      (node (ref "JP4") (pin "2") (pinfunction "2_2") (pintype "passive"))
      (node (ref "JP4") (pin "39") (pinfunction "39_39") (pintype "passive"))
      (node (ref "JP4") (pin "40") (pinfunction "40_40") (pintype "passive"))
      (node (ref "JP5") (pin "1") (pinfunction "1_1") (pintype "passive"))
      (node (ref "JP5") (pin "2") (pinfunction "2_2") (pintype "passive"))
      (node (ref "JP5") (pin "39") (pinfunction "39_39") (pintype "passive"))
      (node (ref "JP5") (pin "40") (pinfunction "40_40") (pintype "passive"))
      (node (ref "JP6") (pin "1") (pinfunction "1_1") (pintype "passive"))
      (node (ref "JP6") (pin "2") (pinfunction "2_2") (pintype "passive"))
      (node (ref "JP6") (pin "39") (pinfunction "39_39") (pintype "passive"))
      (node (ref "JP6") (pin "40") (pinfunction "40_40") (pintype "passive"))
    )
    (net (code "177") (name "unconnected-(IC9-Y4-Pad11)") (class "Default")
      (node (ref "IC9") (pin "11") (pinfunction "Y4_11") (pintype "bidirectional"))
    )
    (net (code "178") (name "unconnected-(IC9-Y5-Pad10)") (class "Default")
      (node (ref "IC9") (pin "10") (pinfunction "Y5_10") (pintype "bidirectional"))
    )
    (net (code "179") (name "unconnected-(IC9-Y6-Pad9)") (class "Default")
      (node (ref "IC9") (pin "9") (pinfunction "Y6_9") (pintype "bidirectional"))
    )
    (net (code "180") (name "unconnected-(IC9-Y7-Pad7)") (class "Default")
      (node (ref "IC9") (pin "7") (pinfunction "Y7_7") (pintype "bidirectional"))
    )
    (net (code "181") (name "unconnected-(IC10-Y4-Pad11)") (class "Default")
      (node (ref "IC10") (pin "11") (pinfunction "Y4_11") (pintype "bidirectional"))
    )
    (net (code "182") (name "unconnected-(IC10-Y5-Pad10)") (class "Default")
      (node (ref "IC10") (pin "10") (pinfunction "Y5_10") (pintype "bidirectional"))
    )
    (net (code "183") (name "unconnected-(IC10-Y6-Pad9)") (class "Default")
      (node (ref "IC10") (pin "9") (pinfunction "Y6_9") (pintype "bidirectional"))
    )
    (net (code "184") (name "unconnected-(IC10-Y7-Pad7)") (class "Default")
      (node (ref "IC10") (pin "7") (pinfunction "Y7_7") (pintype "bidirectional"))
    )
    (net (code "185") (name "unconnected-(JP4-Pad21)") (class "Default")
      (node (ref "JP4") (pin "21") (pinfunction "21_21") (pintype "passive"))
    )
    (net (code "186") (name "unconnected-(JP4-Pad22)") (class "Default")
      (node (ref "JP4") (pin "22") (pinfunction "22_22") (pintype "passive"))
    )
    (net (code "187") (name "unconnected-(JP4-Pad23)") (class "Default")
      (node (ref "JP4") (pin "23") (pinfunction "23_23") (pintype "passive"))
    )
    (net (code "188") (name "unconnected-(JP4-Pad24)") (class "Default")
      (node (ref "JP4") (pin "24") (pinfunction "24_24") (pintype "passive"))
    )
    (net (code "189") (name "unconnected-(JP4-Pad25)") (class "Default")
      (node (ref "JP4") (pin "25") (pinfunction "25_25") (pintype "passive"))
    )
    (net (code "190") (name "unconnected-(JP4-Pad26)") (class "Default")
      (node (ref "JP4") (pin "26") (pinfunction "26_26") (pintype "passive"))
    )
    (net (code "191") (name "unconnected-(JP4-Pad27)") (class "Default")
      (node (ref "JP4") (pin "27") (pinfunction "27_27") (pintype "passive"))
    )
    (net (code "192") (name "unconnected-(JP4-Pad28)") (class "Default")
      (node (ref "JP4") (pin "28") (pinfunction "28_28") (pintype "passive"))
    )
    (net (code "193") (name "unconnected-(JP4-Pad29)") (class "Default")
      (node (ref "JP4") (pin "29") (pinfunction "29_29") (pintype "passive"))
    )
    (net (code "194") (name "unconnected-(JP4-Pad30)") (class "Default")
      (node (ref "JP4") (pin "30") (pinfunction "30_30") (pintype "passive"))
    )
    (net (code "195") (name "unconnected-(JP4-Pad31)") (class "Default")
      (node (ref "JP4") (pin "31") (pinfunction "31_31") (pintype "passive"))
    )
    (net (code "196") (name "unconnected-(JP4-Pad32)") (class "Default")
      (node (ref "JP4") (pin "32") (pinfunction "32_32") (pintype "passive"))
    )
    (net (code "197") (name "unconnected-(JP4-Pad33)") (class "Default")
      (node (ref "JP4") (pin "33") (pinfunction "33_33") (pintype "passive"))
    )
    (net (code "198") (name "unconnected-(JP4-Pad34)") (class "Default")
      (node (ref "JP4") (pin "34") (pinfunction "34_34") (pintype "passive"))
    )
    (net (code "199") (name "unconnected-(JP4-Pad35)") (class "Default")
      (node (ref "JP4") (pin "35") (pinfunction "35_35") (pintype "passive"))
    )
    (net (code "200") (name "unconnected-(JP4-Pad36)") (class "Default")
      (node (ref "JP4") (pin "36") (pinfunction "36_36") (pintype "passive"))
    )
    (net (code "201") (name "unconnected-(JP6-Pad21)") (class "Default")
      (node (ref "JP6") (pin "21") (pinfunction "21_21") (pintype "passive"))
    )
    (net (code "202") (name "unconnected-(JP6-Pad22)") (class "Default")
      (node (ref "JP6") (pin "22") (pinfunction "22_22") (pintype "passive"))
    )
    (net (code "203") (name "unconnected-(JP6-Pad23)") (class "Default")
      (node (ref "JP6") (pin "23") (pinfunction "23_23") (pintype "passive"))
    )
    (net (code "204") (name "unconnected-(JP6-Pad24)") (class "Default")
      (node (ref "JP6") (pin "24") (pinfunction "24_24") (pintype "passive"))
    )
    (net (code "205") (name "unconnected-(JP6-Pad25)") (class "Default")
      (node (ref "JP6") (pin "25") (pinfunction "25_25") (pintype "passive"))
    )
    (net (code "206") (name "unconnected-(JP6-Pad26)") (class "Default")
      (node (ref "JP6") (pin "26") (pinfunction "26_26") (pintype "passive"))
    )
    (net (code "207") (name "unconnected-(JP6-Pad27)") (class "Default")
      (node (ref "JP6") (pin "27") (pinfunction "27_27") (pintype "passive"))
    )
    (net (code "208") (name "unconnected-(JP6-Pad28)") (class "Default")
      (node (ref "JP6") (pin "28") (pinfunction "28_28") (pintype "passive"))
    )
    (net (code "209") (name "unconnected-(JP6-Pad29)") (class "Default")
      (node (ref "JP6") (pin "29") (pinfunction "29_29") (pintype "passive"))
    )
    (net (code "210") (name "unconnected-(JP6-Pad30)") (class "Default")
      (node (ref "JP6") (pin "30") (pinfunction "30_30") (pintype "passive"))
    )
    (net (code "211") (name "unconnected-(JP6-Pad31)") (class "Default")
      (node (ref "JP6") (pin "31") (pinfunction "31_31") (pintype "passive"))
    )
    (net (code "212") (name "unconnected-(JP6-Pad32)") (class "Default")
      (node (ref "JP6") (pin "32") (pinfunction "32_32") (pintype "passive"))
    )
    (net (code "213") (name "unconnected-(JP6-Pad33)") (class "Default")
      (node (ref "JP6") (pin "33") (pinfunction "33_33") (pintype "passive"))
    )
    (net (code "214") (name "unconnected-(JP6-Pad34)") (class "Default")
      (node (ref "JP6") (pin "34") (pinfunction "34_34") (pintype "passive"))
    )
    (net (code "215") (name "unconnected-(JP6-Pad35)") (class "Default")
      (node (ref "JP6") (pin "35") (pinfunction "35_35") (pintype "passive"))
    )
    (net (code "216") (name "unconnected-(JP6-Pad36)") (class "Default")
      (node (ref "JP6") (pin "36") (pinfunction "36_36") (pintype "passive"))
    )
  )
)
